# arca-2_0.net
KiCad netlist of a schematic drawn in EAGLE
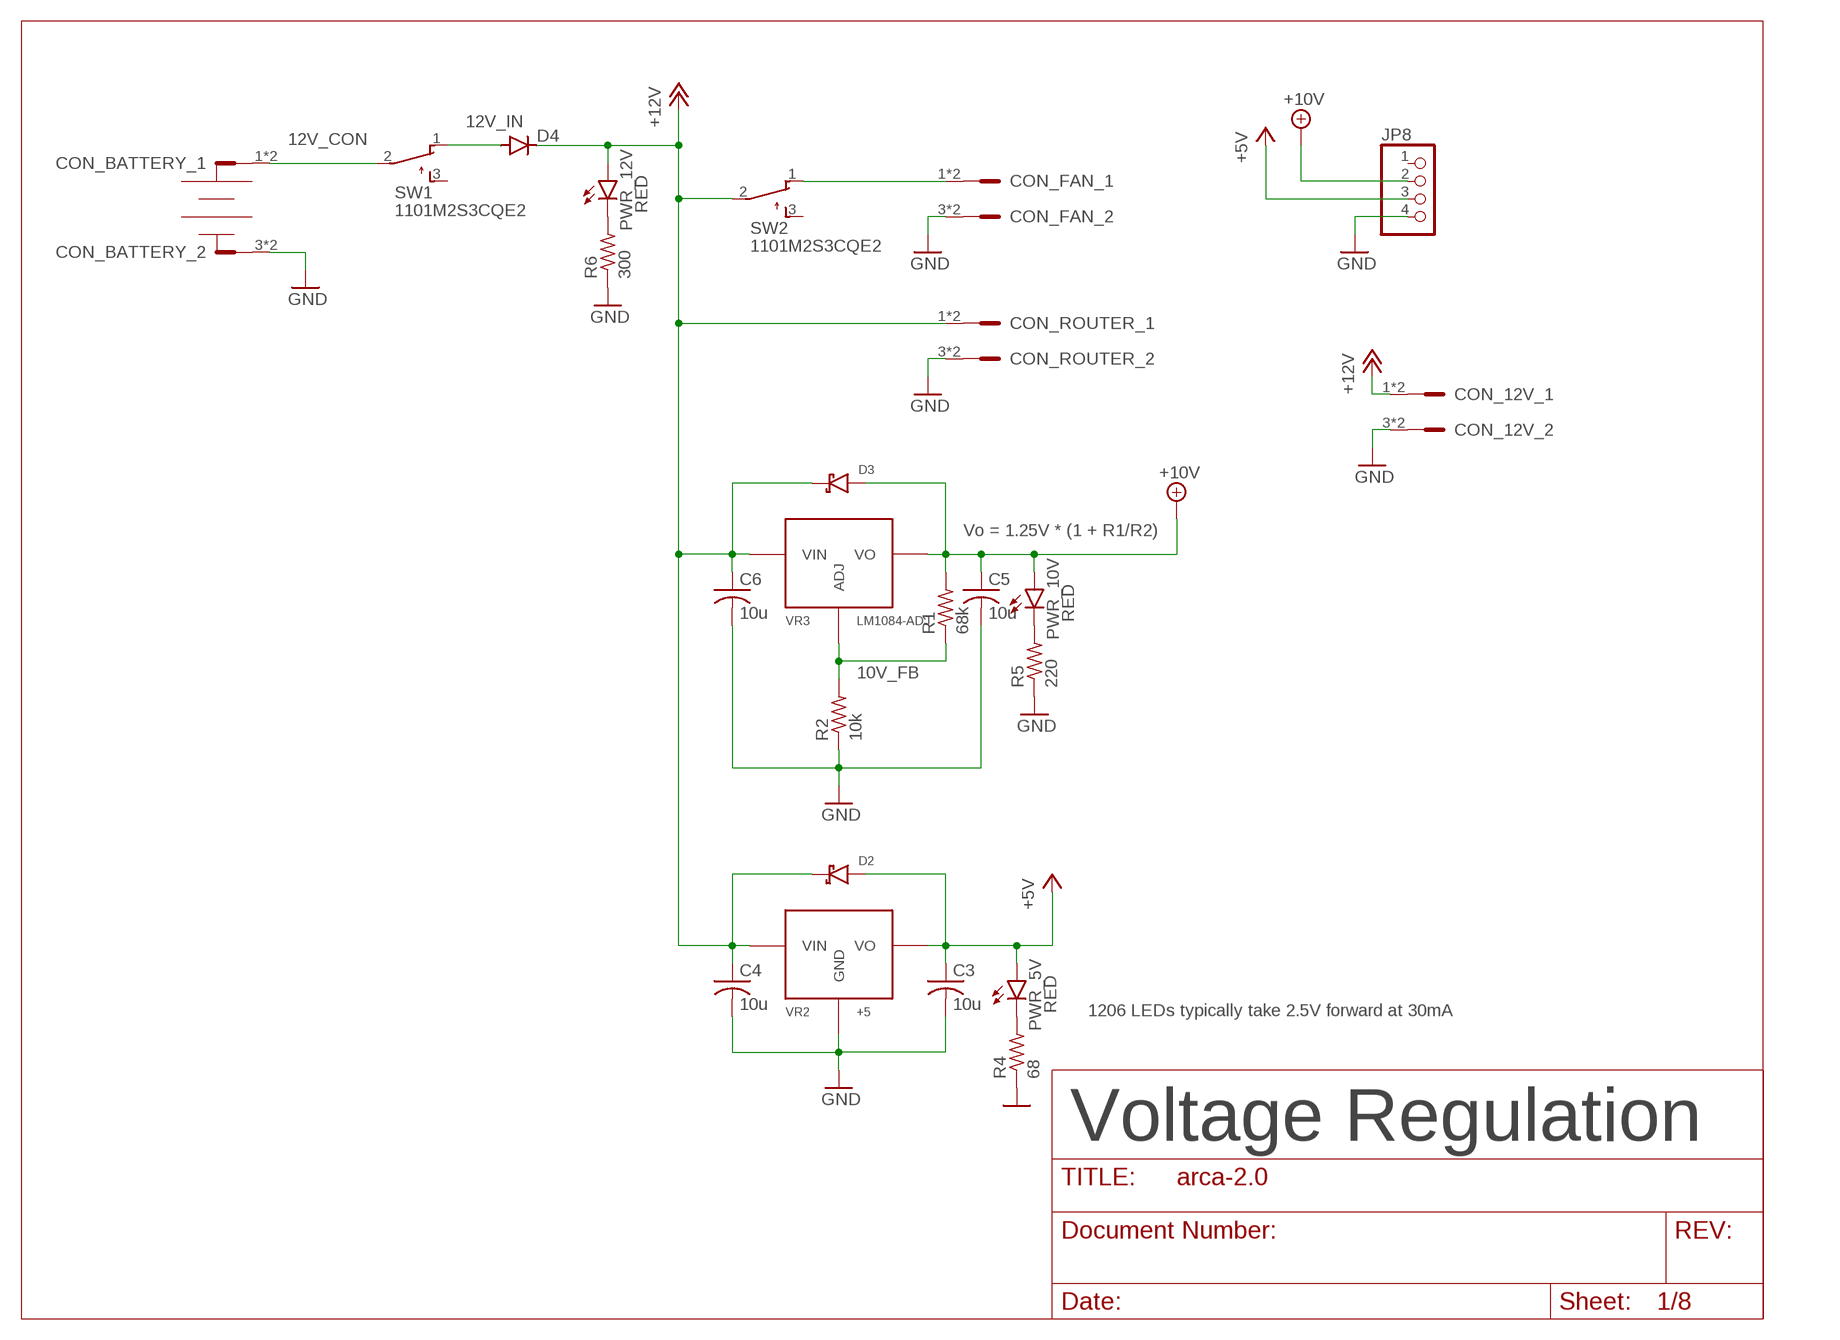
[diagram p0: schematic, sheet 1]
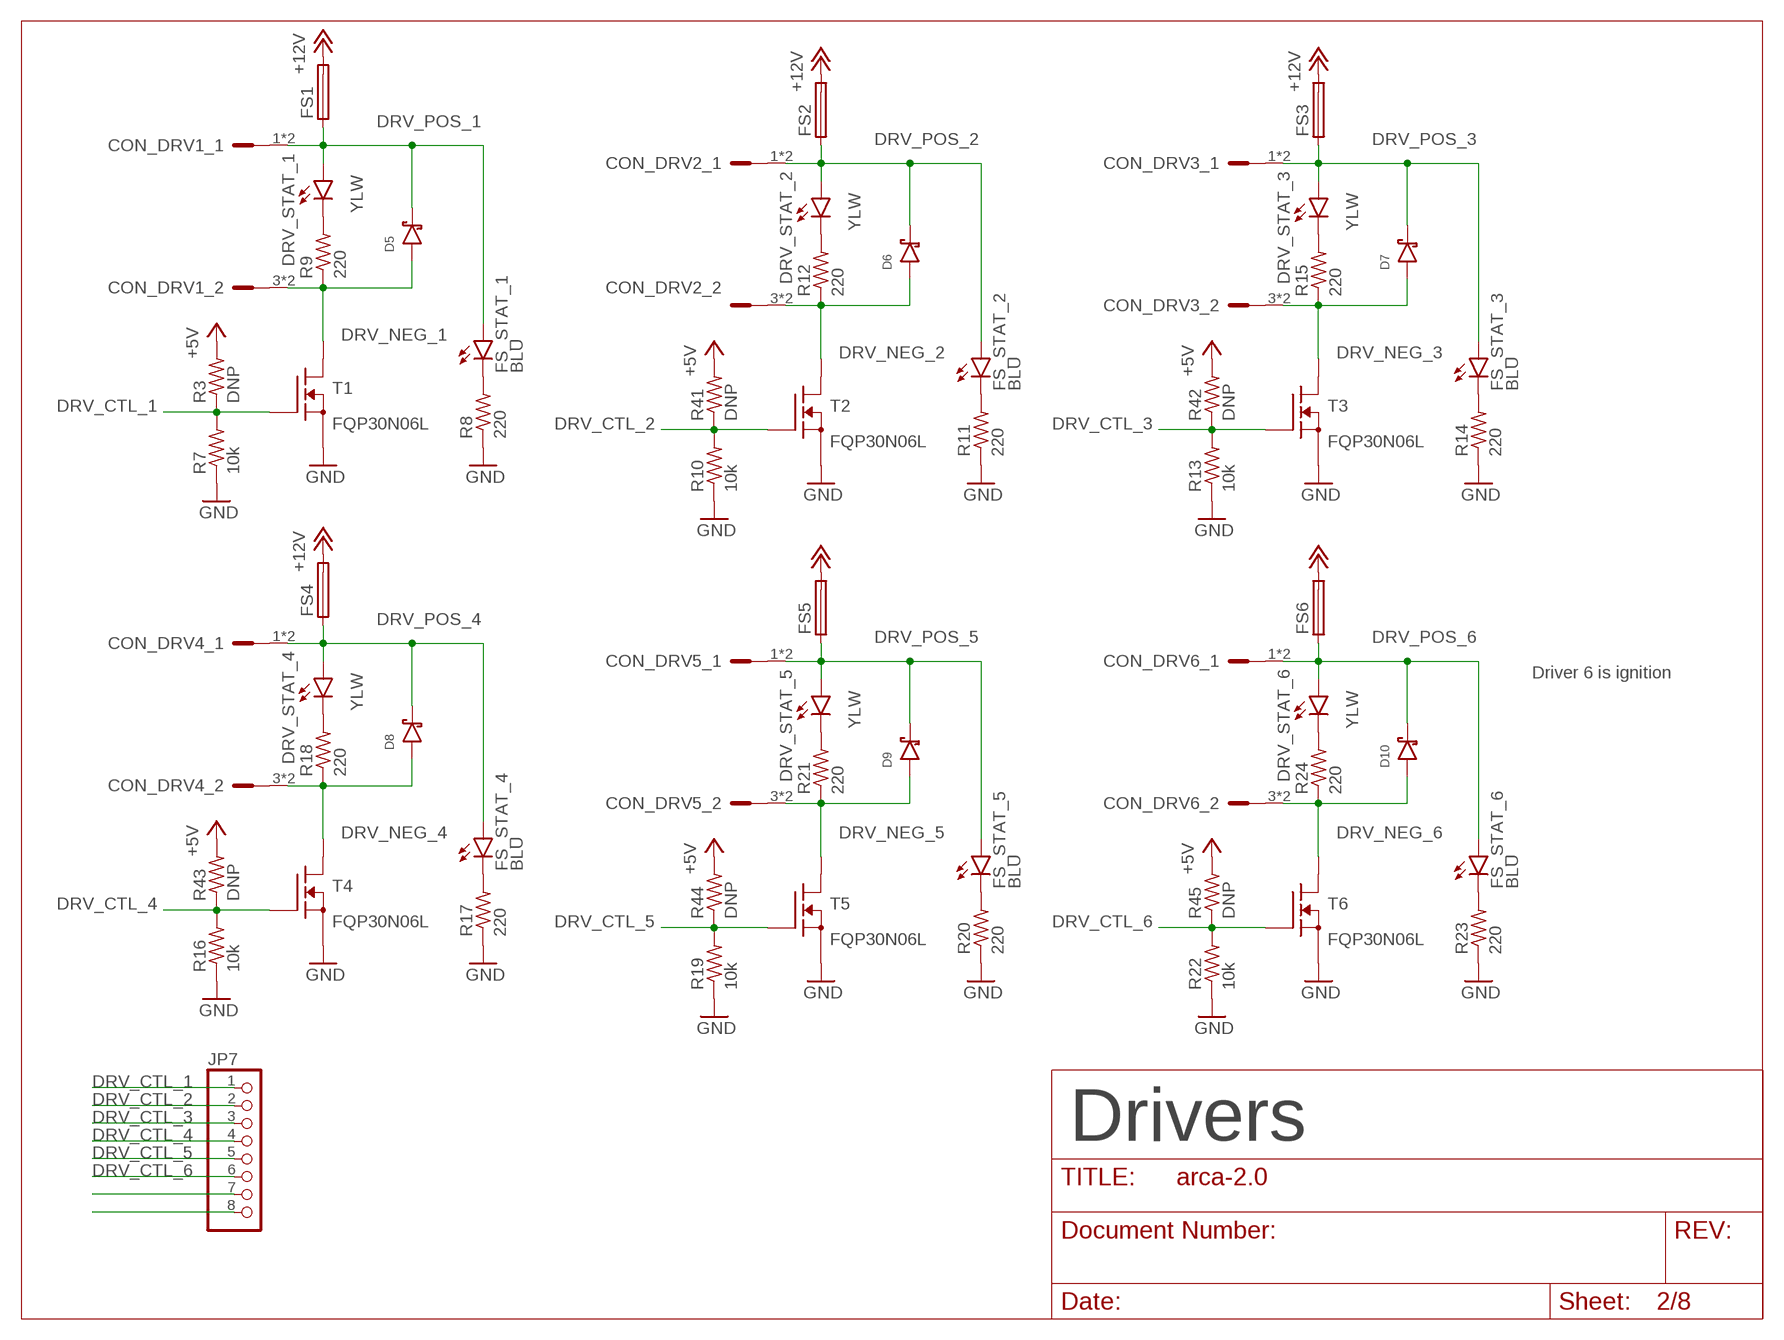
[diagram p1: schematic, sheet 2]
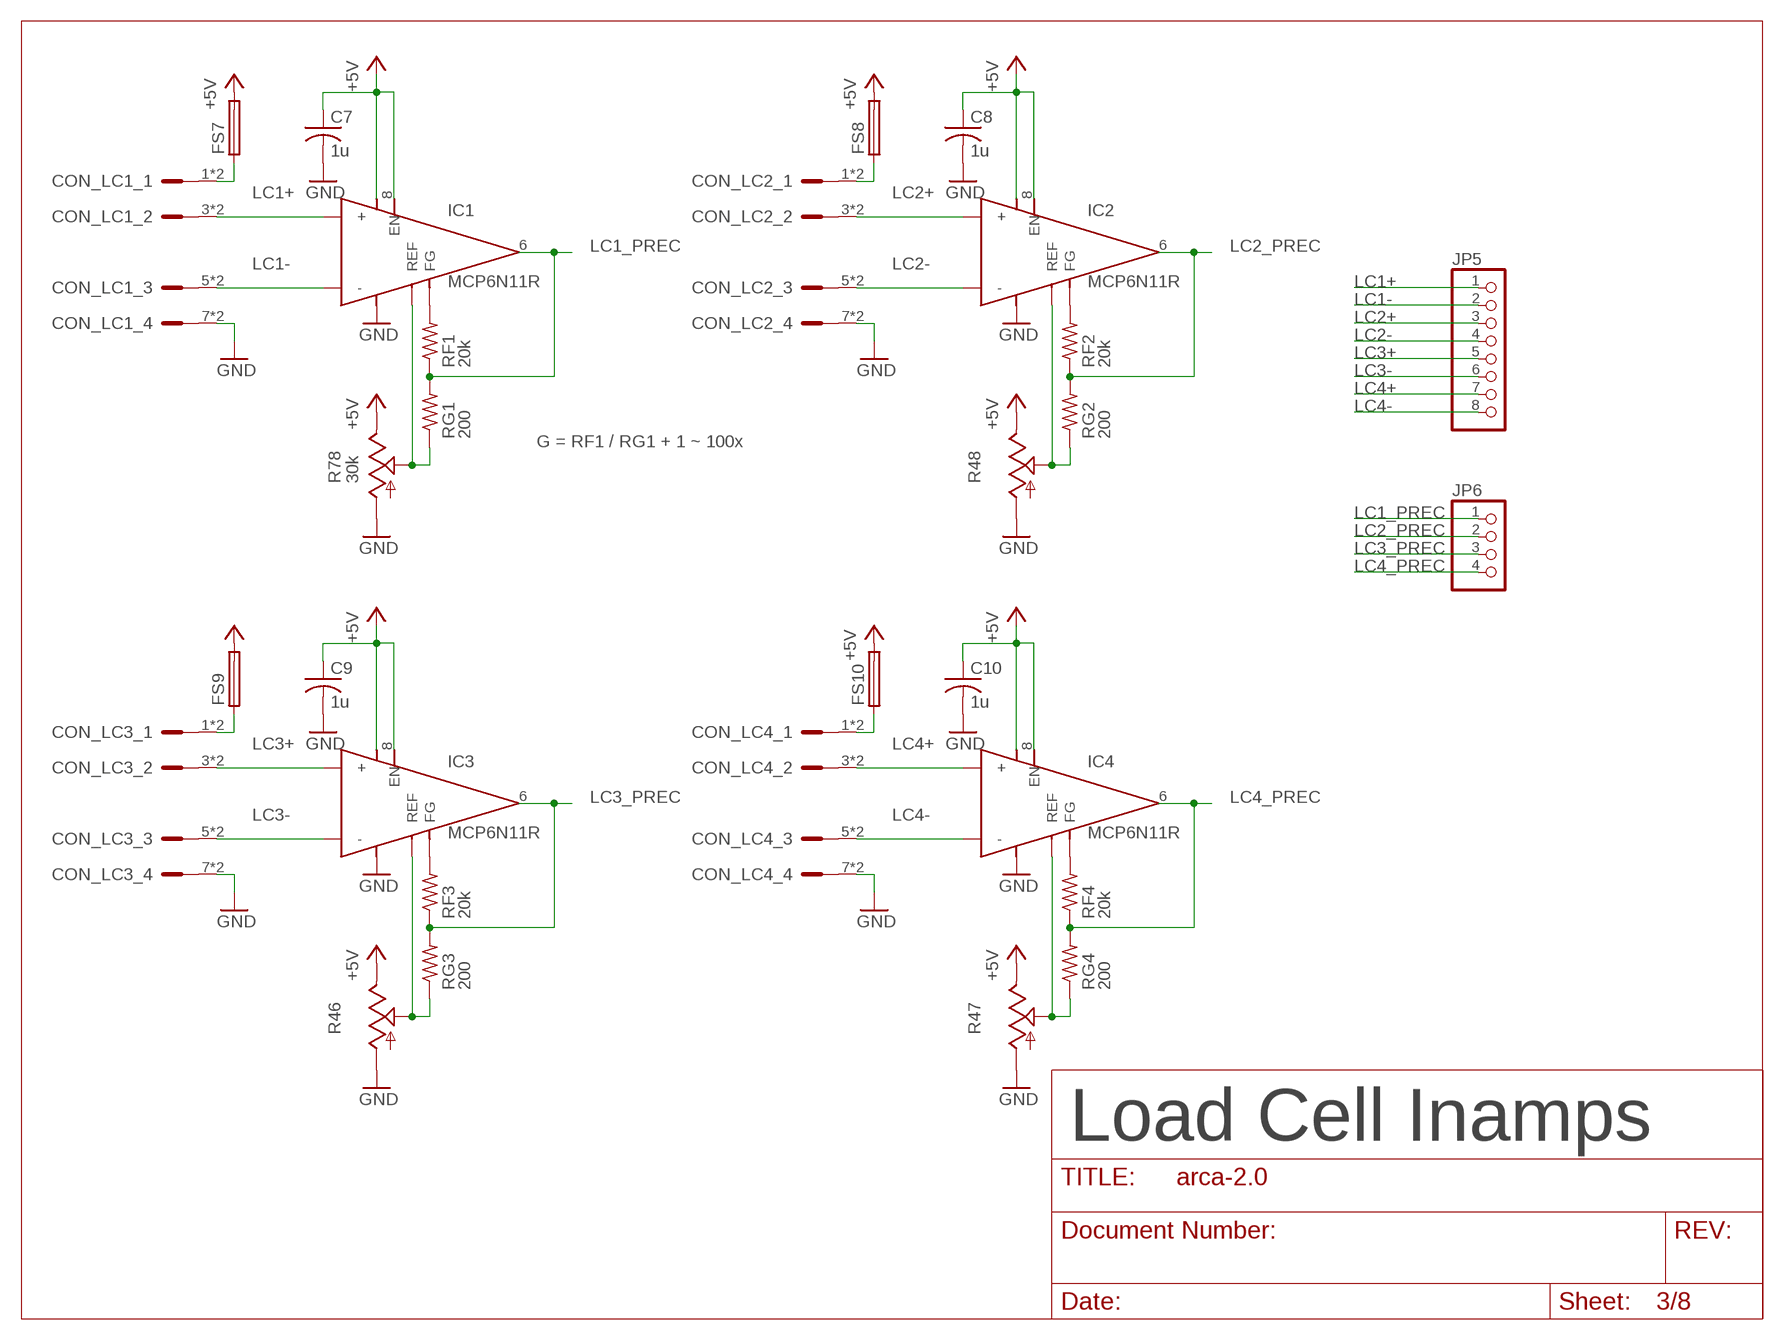
[diagram p2: schematic, sheet 3]
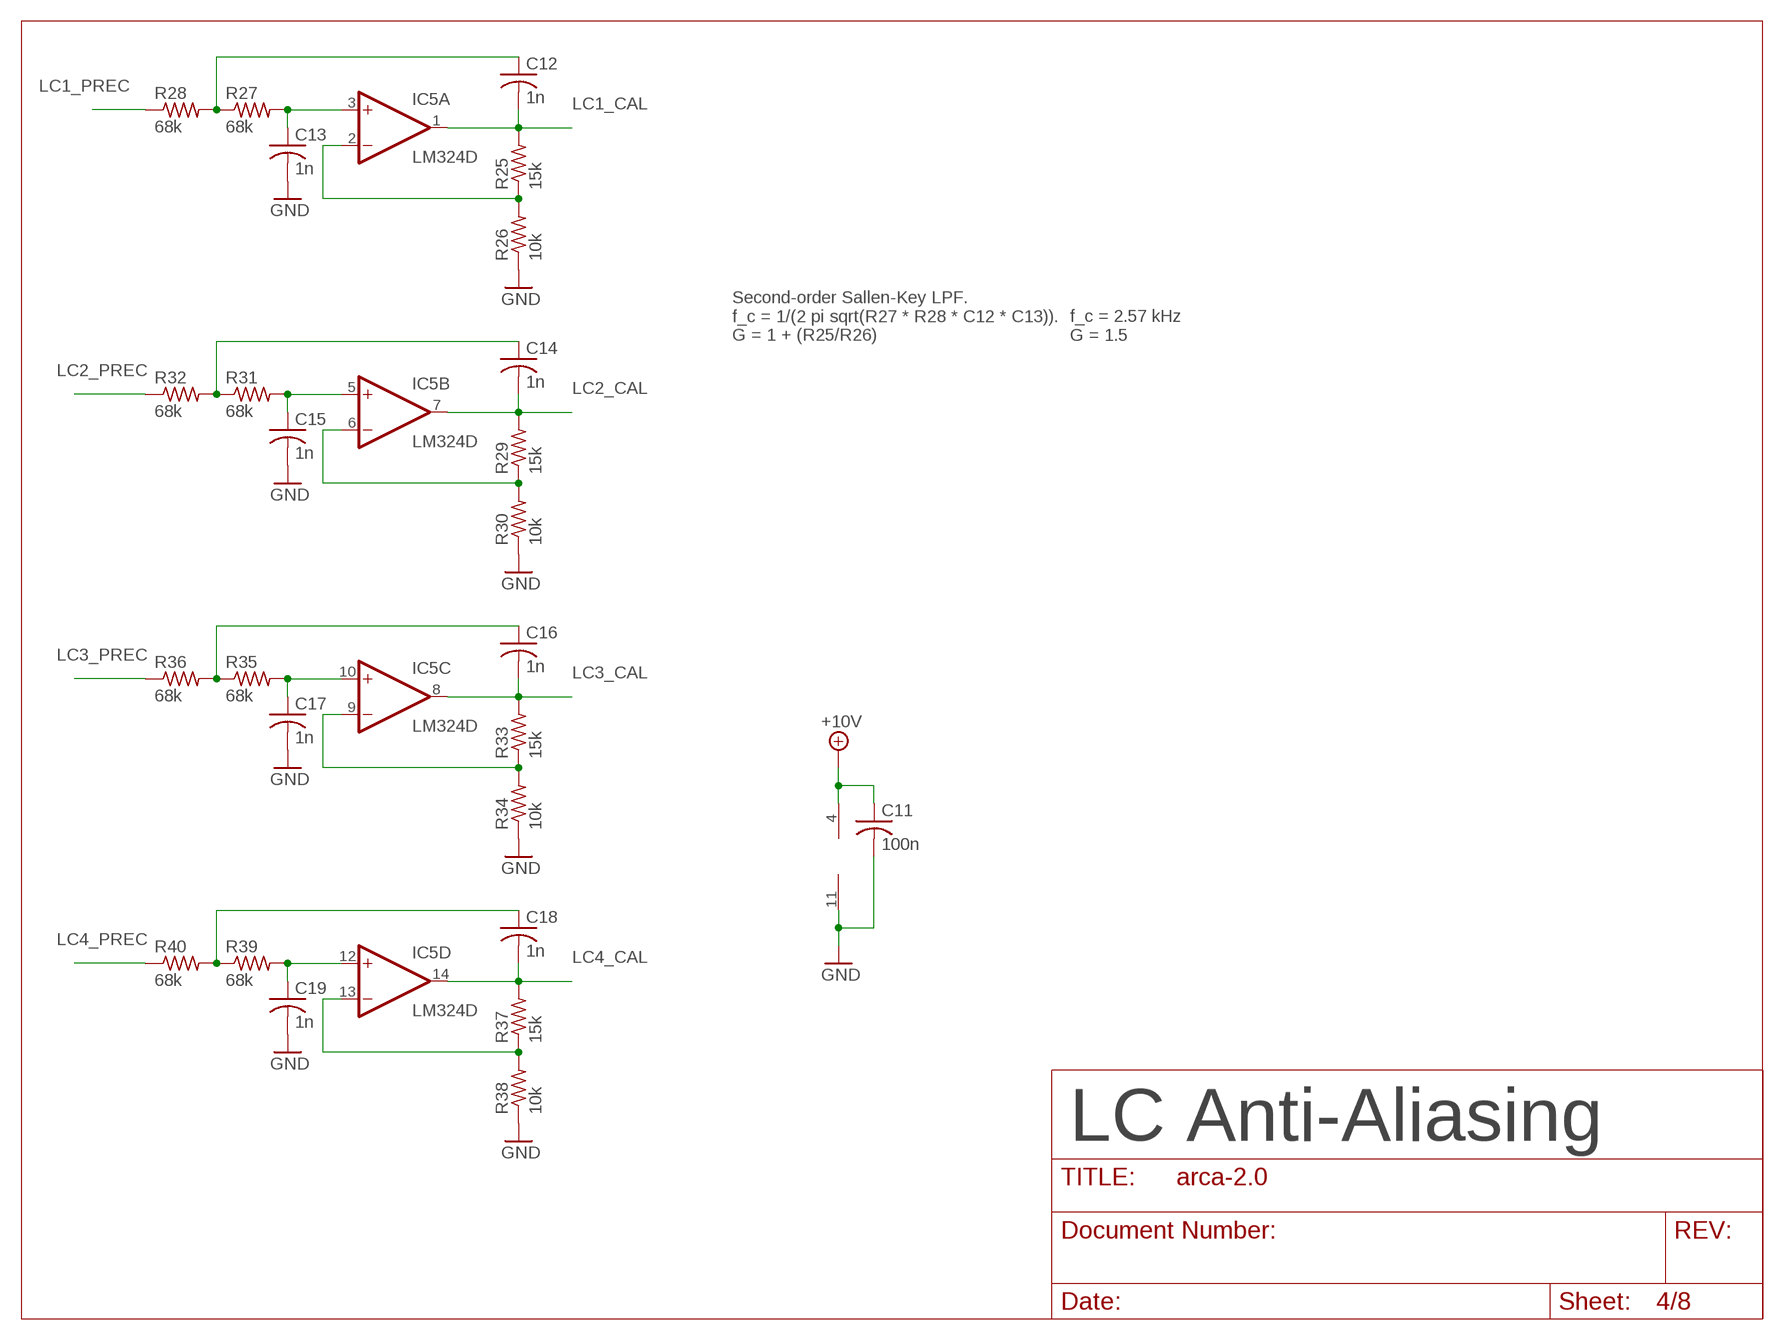
[diagram p3: schematic, sheet 4]
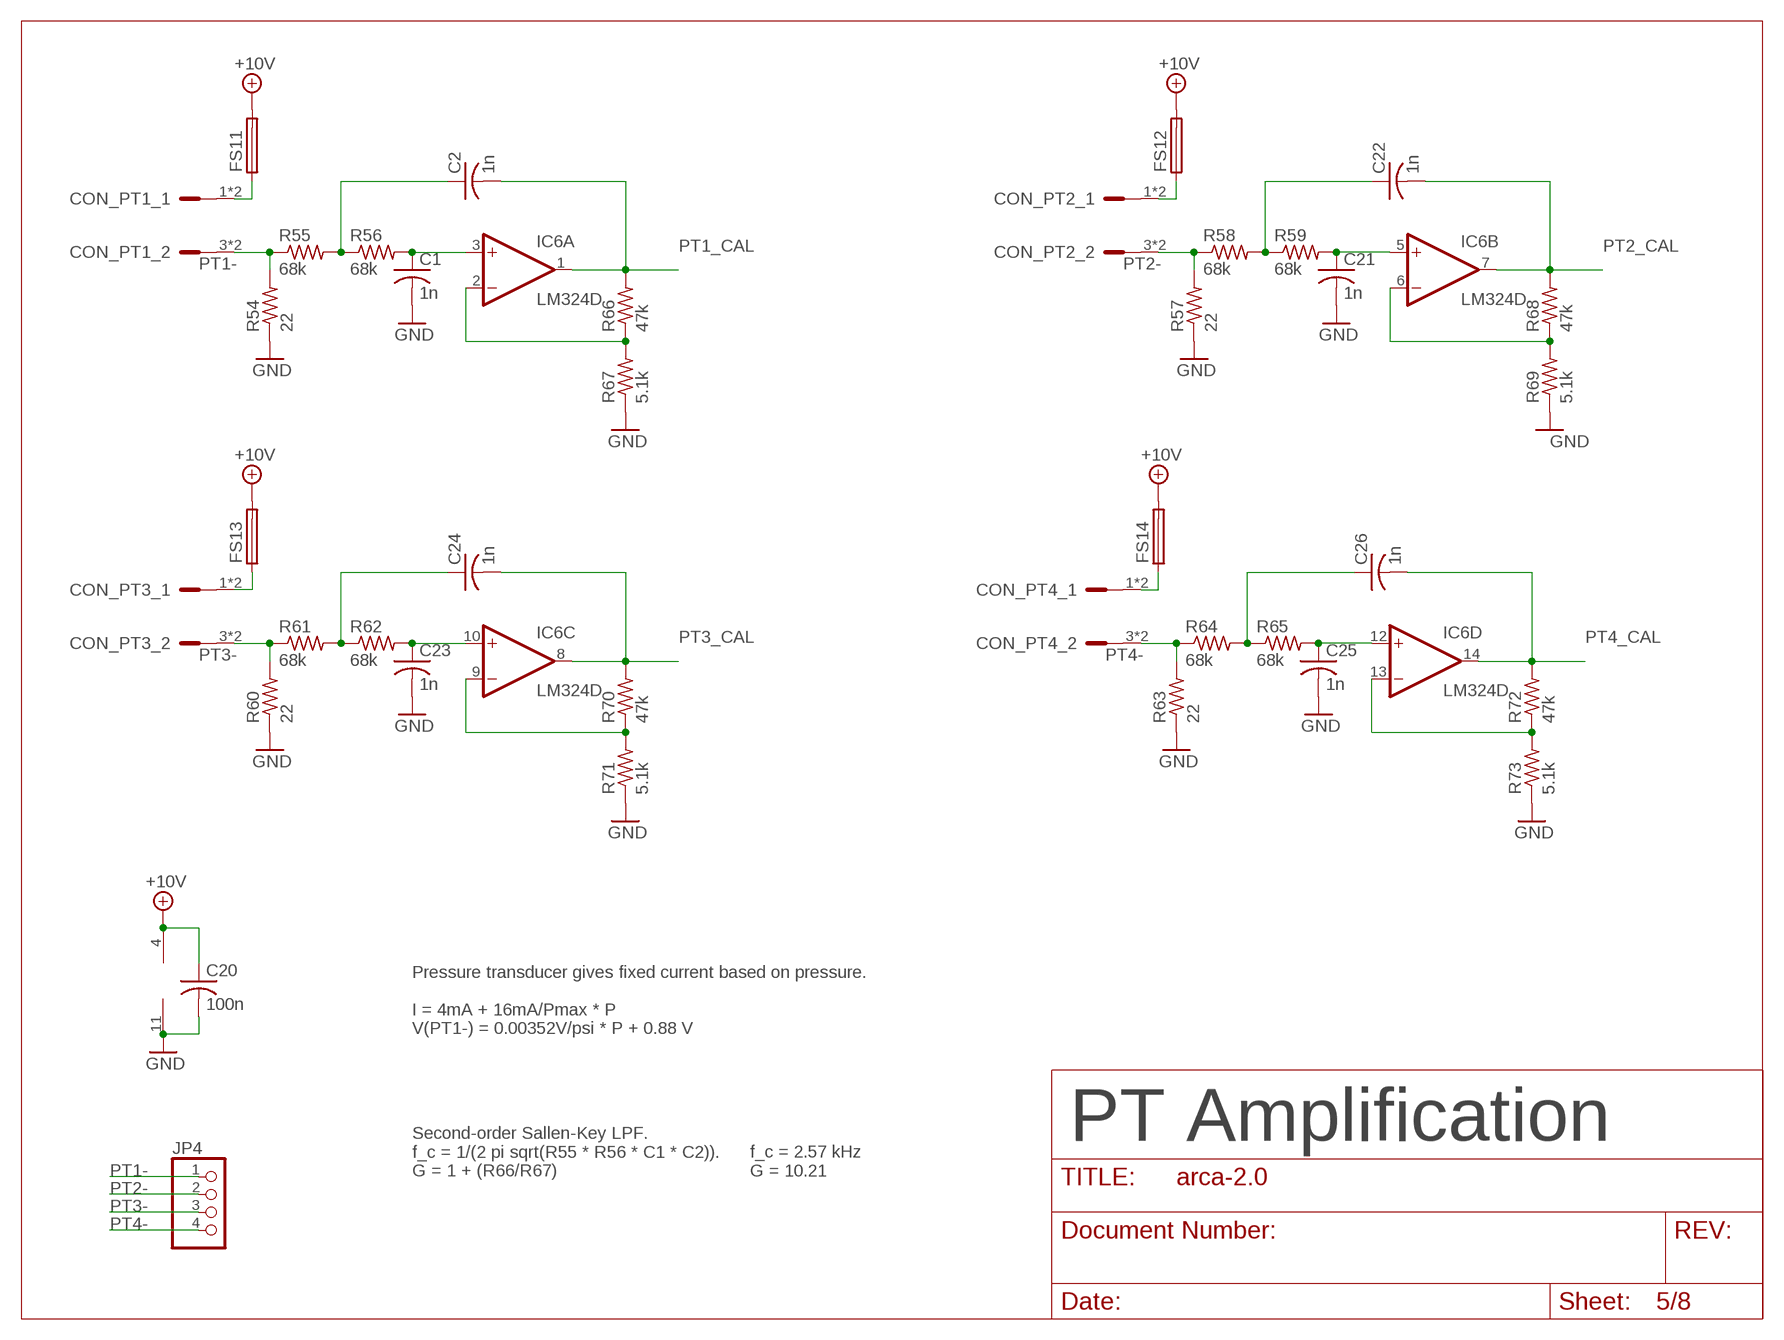
[diagram p4: schematic, sheet 5]
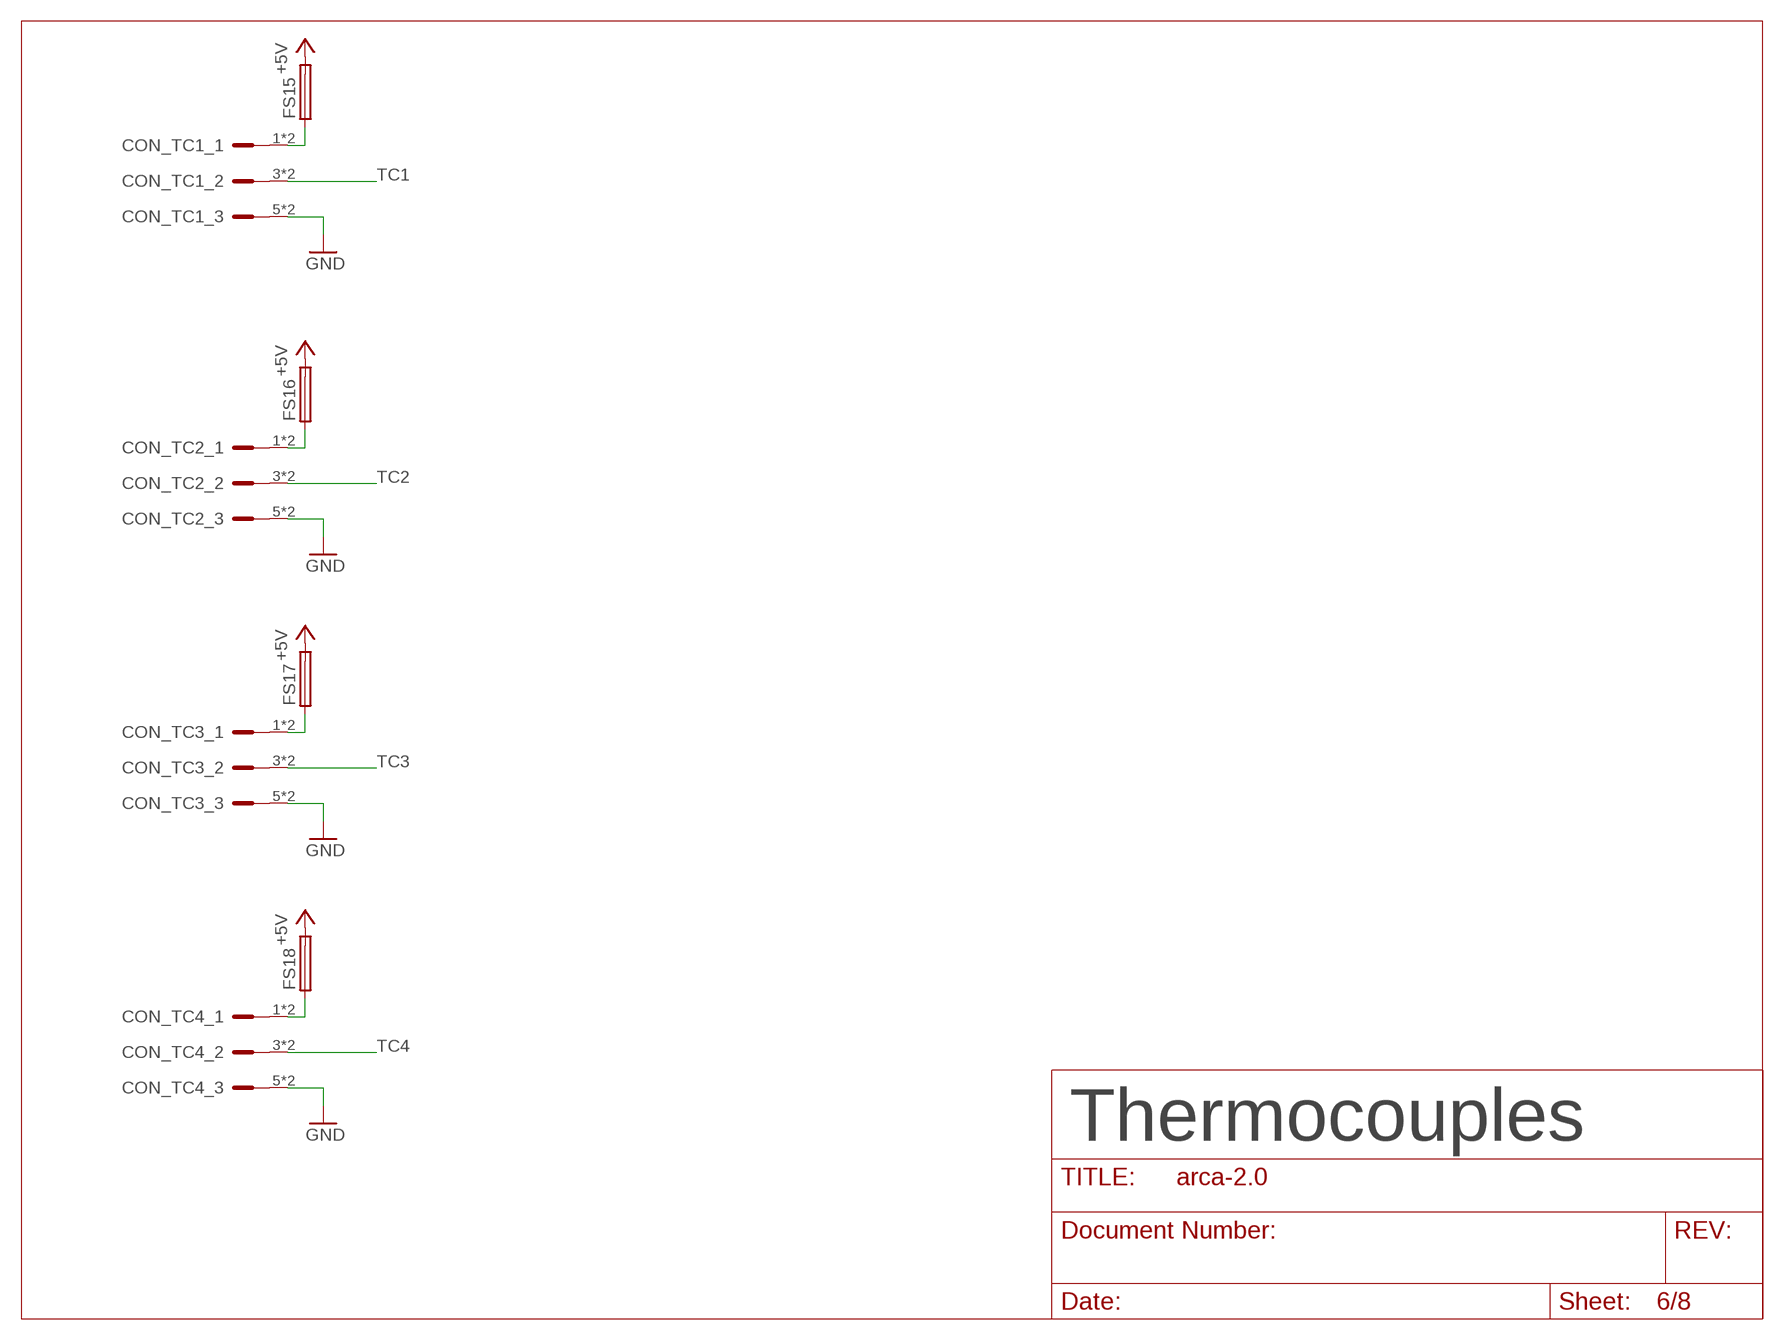
[diagram p5: schematic, sheet 6]
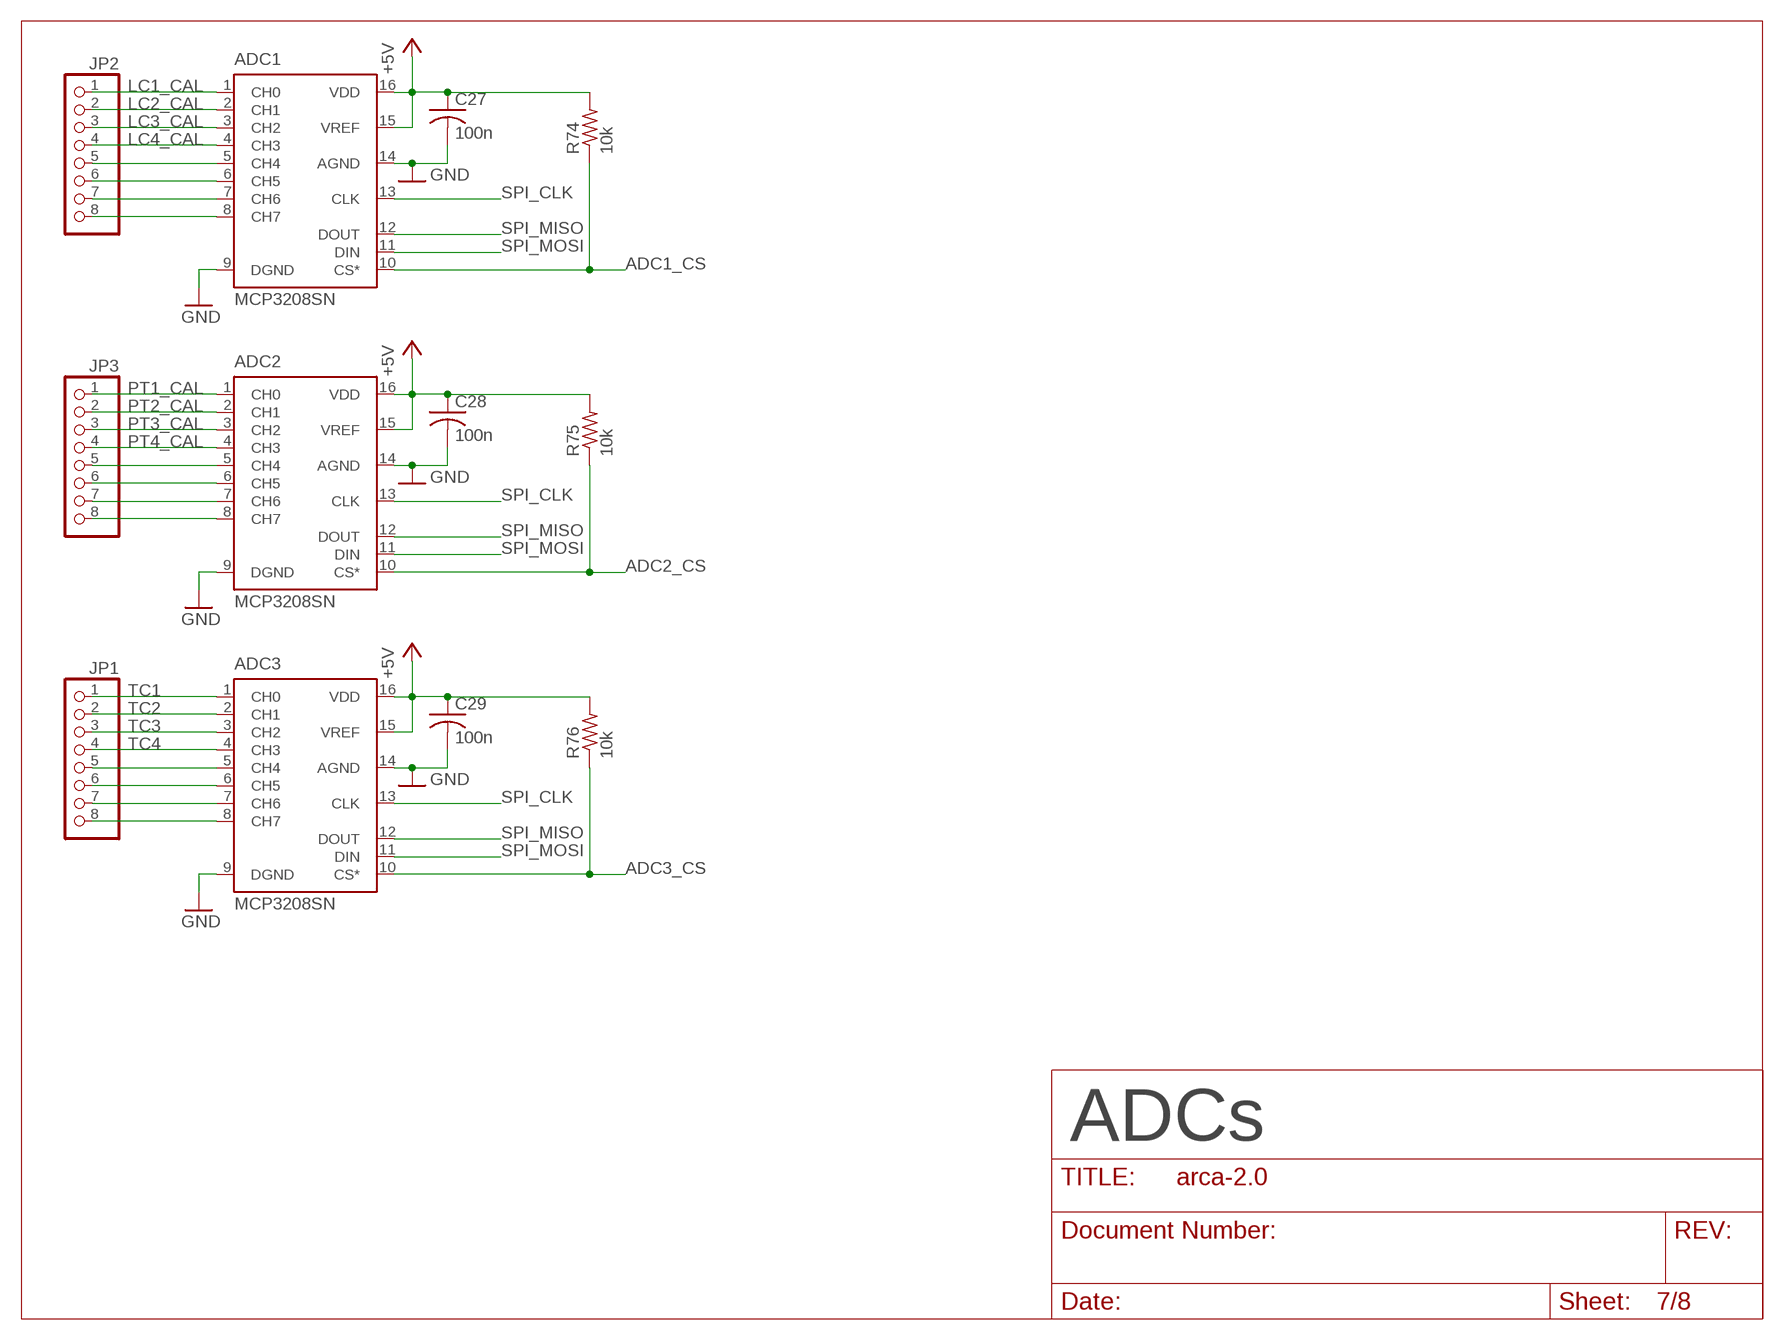
[diagram p6: schematic, sheet 7]
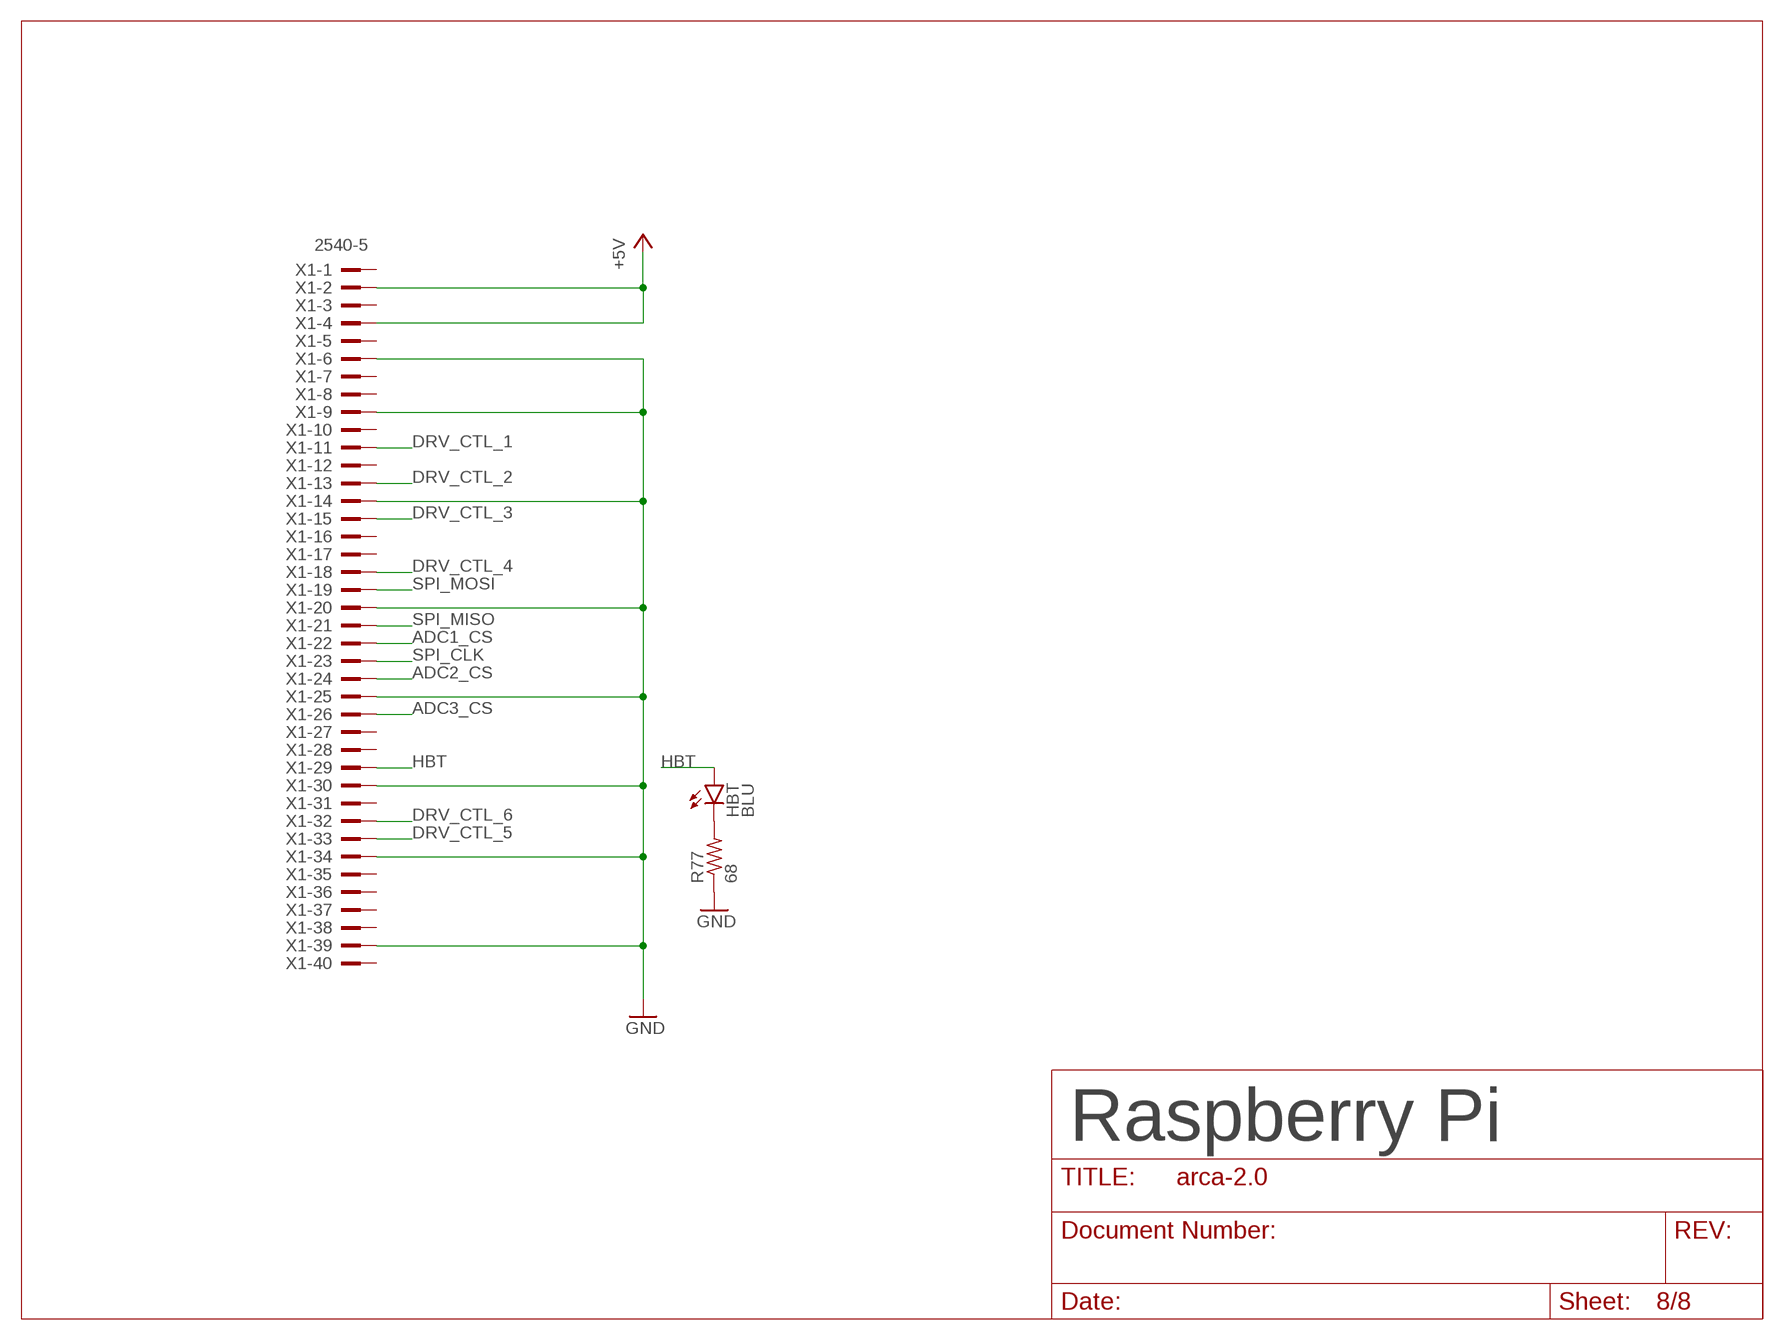
[diagram p7: schematic, sheet 8]

(export (version "E")
  (design (tool "Eeschema 10.0.6"))
  (components
    (comp (ref "HBT")
      (value "BLU")
      (footprint "eagle-import:CHIPLED_1206")
      (libsource (lib "eagle-import") (part "LEDCHIPLED_1206"))
    )
    (comp (ref "R77")
      (value "68")
      (footprint "eagle-import:R1206")
      (libsource (lib "eagle-import") (part "R-US_R1206"))
    )
    (comp (ref "X1")
      (value "2540-5")
      (footprint "eagle-import:PAK100_2500-5-40")
      (libsource (lib "eagle-import") (part "2540-5"))
    )
    (comp (ref "ADC1")
      (value "MCP3208SN")
      (footprint "eagle-import:SO-16")
      (fields (field (name "MF") "MICROCHIP") (field (name "MPN") "MCP3202-CI/SN"))
      (libsource (lib "eagle-import") (part "MCP3208SN"))
    )
    (comp (ref "ADC2")
      (value "MCP3208SN")
      (footprint "eagle-import:SO-16")
      (fields (field (name "MF") "MICROCHIP") (field (name "MPN") "MCP3202-CI/SN"))
      (libsource (lib "eagle-import") (part "MCP3208SN"))
    )
    (comp (ref "ADC3")
      (value "MCP3208SN")
      (footprint "eagle-import:SO-16")
      (fields (field (name "MF") "MICROCHIP") (field (name "MPN") "MCP3202-CI/SN"))
      (libsource (lib "eagle-import") (part "MCP3208SN"))
    )
    (comp (ref "C27")
      (value "100n")
      (footprint "eagle-import:C1206")
      (libsource (lib "eagle-import") (part "C-USC1206"))
    )
    (comp (ref "C28")
      (value "100n")
      (footprint "eagle-import:C1206")
      (libsource (lib "eagle-import") (part "C-USC1206"))
    )
    (comp (ref "C29")
      (value "100n")
      (footprint "eagle-import:C1206")
      (libsource (lib "eagle-import") (part "C-USC1206"))
    )
    (comp (ref "JP1")
      (value "PINHD-1X8")
      (footprint "eagle-import:1X08")
      (libsource (lib "eagle-import") (part "PINHD-1X8"))
    )
    (comp (ref "JP2")
      (value "PINHD-1X8")
      (footprint "eagle-import:1X08")
      (libsource (lib "eagle-import") (part "PINHD-1X8"))
    )
    (comp (ref "JP3")
      (value "PINHD-1X8")
      (footprint "eagle-import:1X08")
      (libsource (lib "eagle-import") (part "PINHD-1X8"))
    )
    (comp (ref "R74")
      (value "10k")
      (footprint "eagle-import:R1206")
      (libsource (lib "eagle-import") (part "R-US_R1206"))
    )
    (comp (ref "R75")
      (value "10k")
      (footprint "eagle-import:R1206")
      (libsource (lib "eagle-import") (part "R-US_R1206"))
    )
    (comp (ref "R76")
      (value "10k")
      (footprint "eagle-import:R1206")
      (libsource (lib "eagle-import") (part "R-US_R1206"))
    )
    (comp (ref "CON_TC1")
      (value "LPTA-3POS")
      (footprint "eagle-import:8.2X3")
      (libsource (lib "eagle-import") (part "LPTA-3POS"))
    )
    (comp (ref "CON_TC2")
      (value "LPTA-3POS")
      (footprint "eagle-import:8.2X3")
      (libsource (lib "eagle-import") (part "LPTA-3POS"))
    )
    (comp (ref "CON_TC3")
      (value "LPTA-3POS")
      (footprint "eagle-import:8.2X3")
      (libsource (lib "eagle-import") (part "LPTA-3POS"))
    )
    (comp (ref "CON_TC4")
      (value "LPTA-3POS")
      (footprint "eagle-import:8.2X3")
      (libsource (lib "eagle-import") (part "LPTA-3POS"))
    )
    (comp (ref "FS15")
      (value "HOLDER_3588-20")
      (footprint "eagle-import:3588-20")
      (libsource (lib "eagle-import") (part "HOLDER_3588-20"))
    )
    (comp (ref "FS16")
      (value "HOLDER_3588-20")
      (footprint "eagle-import:3588-20")
      (libsource (lib "eagle-import") (part "HOLDER_3588-20"))
    )
    (comp (ref "FS17")
      (value "HOLDER_3588-20")
      (footprint "eagle-import:3588-20")
      (libsource (lib "eagle-import") (part "HOLDER_3588-20"))
    )
    (comp (ref "FS18")
      (value "HOLDER_3588-20")
      (footprint "eagle-import:3588-20")
      (libsource (lib "eagle-import") (part "HOLDER_3588-20"))
    )
    (comp (ref "CON_DRV1")
      (value "LPTA-2POS")
      (footprint "eagle-import:8.2X2")
      (libsource (lib "eagle-import") (part "LPTA-2POS"))
    )
    (comp (ref "CON_DRV2")
      (value "LPTA-2POS")
      (footprint "eagle-import:8.2X2")
      (libsource (lib "eagle-import") (part "LPTA-2POS"))
    )
    (comp (ref "CON_DRV3")
      (value "LPTA-2POS")
      (footprint "eagle-import:8.2X2")
      (libsource (lib "eagle-import") (part "LPTA-2POS"))
    )
    (comp (ref "CON_DRV4")
      (value "LPTA-2POS")
      (footprint "eagle-import:8.2X2")
      (libsource (lib "eagle-import") (part "LPTA-2POS"))
    )
    (comp (ref "CON_DRV5")
      (value "LPTA-2POS")
      (footprint "eagle-import:8.2X2")
      (libsource (lib "eagle-import") (part "LPTA-2POS"))
    )
    (comp (ref "CON_DRV6")
      (value "LPTA-2POS")
      (footprint "eagle-import:8.2X2")
      (libsource (lib "eagle-import") (part "LPTA-2POS"))
    )
    (comp (ref "D5")
      (value "SS54")
      (footprint "eagle-import:SS_")
      (libsource (lib "eagle-import") (part "SS54"))
    )
    (comp (ref "D6")
      (value "SS54")
      (footprint "eagle-import:SS_")
      (libsource (lib "eagle-import") (part "SS54"))
    )
    (comp (ref "D7")
      (value "SS54")
      (footprint "eagle-import:SS_")
      (libsource (lib "eagle-import") (part "SS54"))
    )
    (comp (ref "D8")
      (value "SS54")
      (footprint "eagle-import:SS_")
      (libsource (lib "eagle-import") (part "SS54"))
    )
    (comp (ref "D9")
      (value "SS54")
      (footprint "eagle-import:SS_")
      (libsource (lib "eagle-import") (part "SS54"))
    )
    (comp (ref "D10")
      (value "SS54")
      (footprint "eagle-import:SS_")
      (libsource (lib "eagle-import") (part "SS54"))
    )
    (comp (ref "DRV_STAT_1")
      (value "YLW")
      (footprint "eagle-import:CHIPLED_1206")
      (libsource (lib "eagle-import") (part "LEDCHIPLED_1206"))
    )
    (comp (ref "DRV_STAT_2")
      (value "YLW")
      (footprint "eagle-import:CHIPLED_1206")
      (libsource (lib "eagle-import") (part "LEDCHIPLED_1206"))
    )
    (comp (ref "DRV_STAT_3")
      (value "YLW")
      (footprint "eagle-import:CHIPLED_1206")
      (libsource (lib "eagle-import") (part "LEDCHIPLED_1206"))
    )
    (comp (ref "DRV_STAT_4")
      (value "YLW")
      (footprint "eagle-import:CHIPLED_1206")
      (libsource (lib "eagle-import") (part "LEDCHIPLED_1206"))
    )
    (comp (ref "DRV_STAT_5")
      (value "YLW")
      (footprint "eagle-import:CHIPLED_1206")
      (libsource (lib "eagle-import") (part "LEDCHIPLED_1206"))
    )
    (comp (ref "DRV_STAT_6")
      (value "YLW")
      (footprint "eagle-import:CHIPLED_1206")
      (libsource (lib "eagle-import") (part "LEDCHIPLED_1206"))
    )
    (comp (ref "FS1")
      (value "HOLDER_3588-20")
      (footprint "eagle-import:3588-20")
      (libsource (lib "eagle-import") (part "HOLDER_3588-20"))
    )
    (comp (ref "FS2")
      (value "HOLDER_3588-20")
      (footprint "eagle-import:3588-20")
      (libsource (lib "eagle-import") (part "HOLDER_3588-20"))
    )
    (comp (ref "FS3")
      (value "HOLDER_3588-20")
      (footprint "eagle-import:3588-20")
      (libsource (lib "eagle-import") (part "HOLDER_3588-20"))
    )
    (comp (ref "FS4")
      (value "HOLDER_3588-20")
      (footprint "eagle-import:3588-20")
      (libsource (lib "eagle-import") (part "HOLDER_3588-20"))
    )
    (comp (ref "FS5")
      (value "HOLDER_3588-20")
      (footprint "eagle-import:3588-20")
      (libsource (lib "eagle-import") (part "HOLDER_3588-20"))
    )
    (comp (ref "FS6")
      (value "HOLDER_3588-20")
      (footprint "eagle-import:3588-20")
      (libsource (lib "eagle-import") (part "HOLDER_3588-20"))
    )
    (comp (ref "FS_STAT_1")
      (value "BLU")
      (footprint "eagle-import:CHIPLED_1206")
      (libsource (lib "eagle-import") (part "LEDCHIPLED_1206"))
    )
    (comp (ref "FS_STAT_2")
      (value "BLU")
      (footprint "eagle-import:CHIPLED_1206")
      (libsource (lib "eagle-import") (part "LEDCHIPLED_1206"))
    )
    (comp (ref "FS_STAT_3")
      (value "BLU")
      (footprint "eagle-import:CHIPLED_1206")
      (libsource (lib "eagle-import") (part "LEDCHIPLED_1206"))
    )
    (comp (ref "FS_STAT_4")
      (value "BLU")
      (footprint "eagle-import:CHIPLED_1206")
      (libsource (lib "eagle-import") (part "LEDCHIPLED_1206"))
    )
    (comp (ref "FS_STAT_5")
      (value "BLU")
      (footprint "eagle-import:CHIPLED_1206")
      (libsource (lib "eagle-import") (part "LEDCHIPLED_1206"))
    )
    (comp (ref "FS_STAT_6")
      (value "BLU")
      (footprint "eagle-import:CHIPLED_1206")
      (libsource (lib "eagle-import") (part "LEDCHIPLED_1206"))
    )
    (comp (ref "JP7")
      (value "PINHD-1X8")
      (footprint "eagle-import:1X08")
      (libsource (lib "eagle-import") (part "PINHD-1X8"))
    )
    (comp (ref "R3")
      (value "DNP")
      (footprint "eagle-import:R1206")
      (libsource (lib "eagle-import") (part "R-US_R1206"))
    )
    (comp (ref "R7")
      (value "10k")
      (footprint "eagle-import:R1206")
      (libsource (lib "eagle-import") (part "R-US_R1206"))
    )
    (comp (ref "R8")
      (value "220")
      (footprint "eagle-import:R1206")
      (libsource (lib "eagle-import") (part "R-US_R1206"))
    )
    (comp (ref "R9")
      (value "220")
      (footprint "eagle-import:R1206")
      (libsource (lib "eagle-import") (part "R-US_R1206"))
    )
    (comp (ref "R10")
      (value "10k")
      (footprint "eagle-import:R1206")
      (libsource (lib "eagle-import") (part "R-US_R1206"))
    )
    (comp (ref "R11")
      (value "220")
      (footprint "eagle-import:R1206")
      (libsource (lib "eagle-import") (part "R-US_R1206"))
    )
    (comp (ref "R12")
      (value "220")
      (footprint "eagle-import:R1206")
      (libsource (lib "eagle-import") (part "R-US_R1206"))
    )
    (comp (ref "R13")
      (value "10k")
      (footprint "eagle-import:R1206")
      (libsource (lib "eagle-import") (part "R-US_R1206"))
    )
    (comp (ref "R14")
      (value "220")
      (footprint "eagle-import:R1206")
      (libsource (lib "eagle-import") (part "R-US_R1206"))
    )
    (comp (ref "R15")
      (value "220")
      (footprint "eagle-import:R1206")
      (libsource (lib "eagle-import") (part "R-US_R1206"))
    )
    (comp (ref "R16")
      (value "10k")
      (footprint "eagle-import:R1206")
      (libsource (lib "eagle-import") (part "R-US_R1206"))
    )
    (comp (ref "R17")
      (value "220")
      (footprint "eagle-import:R1206")
      (libsource (lib "eagle-import") (part "R-US_R1206"))
    )
    (comp (ref "R18")
      (value "220")
      (footprint "eagle-import:R1206")
      (libsource (lib "eagle-import") (part "R-US_R1206"))
    )
    (comp (ref "R19")
      (value "10k")
      (footprint "eagle-import:R1206")
      (libsource (lib "eagle-import") (part "R-US_R1206"))
    )
    (comp (ref "R20")
      (value "220")
      (footprint "eagle-import:R1206")
      (libsource (lib "eagle-import") (part "R-US_R1206"))
    )
    (comp (ref "R21")
      (value "220")
      (footprint "eagle-import:R1206")
      (libsource (lib "eagle-import") (part "R-US_R1206"))
    )
    (comp (ref "R22")
      (value "10k")
      (footprint "eagle-import:R1206")
      (libsource (lib "eagle-import") (part "R-US_R1206"))
    )
    (comp (ref "R23")
      (value "220")
      (footprint "eagle-import:R1206")
      (libsource (lib "eagle-import") (part "R-US_R1206"))
    )
    (comp (ref "R24")
      (value "220")
      (footprint "eagle-import:R1206")
      (libsource (lib "eagle-import") (part "R-US_R1206"))
    )
    (comp (ref "R41")
      (value "DNP")
      (footprint "eagle-import:R1206")
      (libsource (lib "eagle-import") (part "R-US_R1206"))
    )
    (comp (ref "R42")
      (value "DNP")
      (footprint "eagle-import:R1206")
      (libsource (lib "eagle-import") (part "R-US_R1206"))
    )
    (comp (ref "R43")
      (value "DNP")
      (footprint "eagle-import:R1206")
      (libsource (lib "eagle-import") (part "R-US_R1206"))
    )
    (comp (ref "R44")
      (value "DNP")
      (footprint "eagle-import:R1206")
      (libsource (lib "eagle-import") (part "R-US_R1206"))
    )
    (comp (ref "R45")
      (value "DNP")
      (footprint "eagle-import:R1206")
      (libsource (lib "eagle-import") (part "R-US_R1206"))
    )
    (comp (ref "T1")
      (value "FQP30N06L")
      (footprint "eagle-import:TO220V")
      (libsource (lib "eagle-import") (part "FQP30N06L"))
    )
    (comp (ref "T2")
      (value "FQP30N06L")
      (footprint "eagle-import:TO220V")
      (libsource (lib "eagle-import") (part "FQP30N06L"))
    )
    (comp (ref "T3")
      (value "FQP30N06L")
      (footprint "eagle-import:TO220V")
      (libsource (lib "eagle-import") (part "FQP30N06L"))
    )
    (comp (ref "T4")
      (value "FQP30N06L")
      (footprint "eagle-import:TO220V")
      (libsource (lib "eagle-import") (part "FQP30N06L"))
    )
    (comp (ref "T5")
      (value "FQP30N06L")
      (footprint "eagle-import:TO220V")
      (libsource (lib "eagle-import") (part "FQP30N06L"))
    )
    (comp (ref "T6")
      (value "FQP30N06L")
      (footprint "eagle-import:TO220V")
      (libsource (lib "eagle-import") (part "FQP30N06L"))
    )
    (comp (ref "C1")
      (value "1n")
      (footprint "eagle-import:C1206")
      (libsource (lib "eagle-import") (part "C-USC1206"))
    )
    (comp (ref "C2")
      (value "1n")
      (footprint "eagle-import:C1206")
      (libsource (lib "eagle-import") (part "C-USC1206"))
    )
    (comp (ref "C20")
      (value "100n")
      (footprint "eagle-import:C1206")
      (libsource (lib "eagle-import") (part "C-USC1206"))
    )
    (comp (ref "C21")
      (value "1n")
      (footprint "eagle-import:C1206")
      (libsource (lib "eagle-import") (part "C-USC1206"))
    )
    (comp (ref "C22")
      (value "1n")
      (footprint "eagle-import:C1206")
      (libsource (lib "eagle-import") (part "C-USC1206"))
    )
    (comp (ref "C23")
      (value "1n")
      (footprint "eagle-import:C1206")
      (libsource (lib "eagle-import") (part "C-USC1206"))
    )
    (comp (ref "C24")
      (value "1n")
      (footprint "eagle-import:C1206")
      (libsource (lib "eagle-import") (part "C-USC1206"))
    )
    (comp (ref "C25")
      (value "1n")
      (footprint "eagle-import:C1206")
      (libsource (lib "eagle-import") (part "C-USC1206"))
    )
    (comp (ref "C26")
      (value "1n")
      (footprint "eagle-import:C1206")
      (libsource (lib "eagle-import") (part "C-USC1206"))
    )
    (comp (ref "CON_PT1")
      (value "LPTA-2POS")
      (footprint "eagle-import:8.2X2")
      (libsource (lib "eagle-import") (part "LPTA-2POS"))
    )
    (comp (ref "CON_PT2")
      (value "LPTA-2POS")
      (footprint "eagle-import:8.2X2")
      (libsource (lib "eagle-import") (part "LPTA-2POS"))
    )
    (comp (ref "CON_PT3")
      (value "LPTA-2POS")
      (footprint "eagle-import:8.2X2")
      (libsource (lib "eagle-import") (part "LPTA-2POS"))
    )
    (comp (ref "CON_PT4")
      (value "LPTA-2POS")
      (footprint "eagle-import:8.2X2")
      (libsource (lib "eagle-import") (part "LPTA-2POS"))
    )
    (comp (ref "FS11")
      (value "HOLDER_3588-20")
      (footprint "eagle-import:3588-20")
      (libsource (lib "eagle-import") (part "HOLDER_3588-20"))
    )
    (comp (ref "FS12")
      (value "HOLDER_3588-20")
      (footprint "eagle-import:3588-20")
      (libsource (lib "eagle-import") (part "HOLDER_3588-20"))
    )
    (comp (ref "FS13")
      (value "HOLDER_3588-20")
      (footprint "eagle-import:3588-20")
      (libsource (lib "eagle-import") (part "HOLDER_3588-20"))
    )
    (comp (ref "FS14")
      (value "HOLDER_3588-20")
      (footprint "eagle-import:3588-20")
      (libsource (lib "eagle-import") (part "HOLDER_3588-20"))
    )
    (comp (ref "IC6")
      (value "LM324D")
      (footprint "eagle-import:SO14")
      (libsource (lib "eagle-import") (part "LM324D"))
    )
    (comp (ref "JP4")
      (value "PINHD-1X4")
      (footprint "eagle-import:1X04")
      (libsource (lib "eagle-import") (part "PINHD-1X4"))
    )
    (comp (ref "R54")
      (value "22")
      (footprint "eagle-import:R1206")
      (libsource (lib "eagle-import") (part "R-US_R1206"))
    )
    (comp (ref "R55")
      (value "68k")
      (footprint "eagle-import:R1206")
      (libsource (lib "eagle-import") (part "R-US_R1206"))
    )
    (comp (ref "R56")
      (value "68k")
      (footprint "eagle-import:R1206")
      (libsource (lib "eagle-import") (part "R-US_R1206"))
    )
    (comp (ref "R57")
      (value "22")
      (footprint "eagle-import:R1206")
      (libsource (lib "eagle-import") (part "R-US_R1206"))
    )
    (comp (ref "R58")
      (value "68k")
      (footprint "eagle-import:R1206")
      (libsource (lib "eagle-import") (part "R-US_R1206"))
    )
    (comp (ref "R59")
      (value "68k")
      (footprint "eagle-import:R1206")
      (libsource (lib "eagle-import") (part "R-US_R1206"))
    )
    (comp (ref "R60")
      (value "22")
      (footprint "eagle-import:R1206")
      (libsource (lib "eagle-import") (part "R-US_R1206"))
    )
    (comp (ref "R61")
      (value "68k")
      (footprint "eagle-import:R1206")
      (libsource (lib "eagle-import") (part "R-US_R1206"))
    )
    (comp (ref "R62")
      (value "68k")
      (footprint "eagle-import:R1206")
      (libsource (lib "eagle-import") (part "R-US_R1206"))
    )
    (comp (ref "R63")
      (value "22")
      (footprint "eagle-import:R1206")
      (libsource (lib "eagle-import") (part "R-US_R1206"))
    )
    (comp (ref "R64")
      (value "68k")
      (footprint "eagle-import:R1206")
      (libsource (lib "eagle-import") (part "R-US_R1206"))
    )
    (comp (ref "R65")
      (value "68k")
      (footprint "eagle-import:R1206")
      (libsource (lib "eagle-import") (part "R-US_R1206"))
    )
    (comp (ref "R66")
      (value "47k")
      (footprint "eagle-import:R1206")
      (libsource (lib "eagle-import") (part "R-US_R1206"))
    )
    (comp (ref "R67")
      (value "5.1k")
      (footprint "eagle-import:R1206")
      (libsource (lib "eagle-import") (part "R-US_R1206"))
    )
    (comp (ref "R68")
      (value "47k")
      (footprint "eagle-import:R1206")
      (libsource (lib "eagle-import") (part "R-US_R1206"))
    )
    (comp (ref "R69")
      (value "5.1k")
      (footprint "eagle-import:R1206")
      (libsource (lib "eagle-import") (part "R-US_R1206"))
    )
    (comp (ref "R70")
      (value "47k")
      (footprint "eagle-import:R1206")
      (libsource (lib "eagle-import") (part "R-US_R1206"))
    )
    (comp (ref "R71")
      (value "5.1k")
      (footprint "eagle-import:R1206")
      (libsource (lib "eagle-import") (part "R-US_R1206"))
    )
    (comp (ref "R72")
      (value "47k")
      (footprint "eagle-import:R1206")
      (libsource (lib "eagle-import") (part "R-US_R1206"))
    )
    (comp (ref "R73")
      (value "5.1k")
      (footprint "eagle-import:R1206")
      (libsource (lib "eagle-import") (part "R-US_R1206"))
    )
    (comp (ref "C3")
      (value "10u")
      (footprint "eagle-import:C1206")
      (libsource (lib "eagle-import") (part "C-USC1206"))
    )
    (comp (ref "C4")
      (value "10u")
      (footprint "eagle-import:C1206")
      (libsource (lib "eagle-import") (part "C-USC1206"))
    )
    (comp (ref "C5")
      (value "10u")
      (footprint "eagle-import:C1206")
      (libsource (lib "eagle-import") (part "C-USC1206"))
    )
    (comp (ref "C6")
      (value "10u")
      (footprint "eagle-import:C1206")
      (libsource (lib "eagle-import") (part "C-USC1206"))
    )
    (comp (ref "CON_12V")
      (value "LPTA-2POS")
      (footprint "eagle-import:8.2X2")
      (libsource (lib "eagle-import") (part "LPTA-2POS"))
    )
    (comp (ref "CON_BATTERY")
      (value "LPTA-2POS")
      (footprint "eagle-import:8.2X2")
      (libsource (lib "eagle-import") (part "LPTA-2POS"))
    )
    (comp (ref "CON_FAN")
      (value "LPTA-2POS")
      (footprint "eagle-import:8.2X2")
      (libsource (lib "eagle-import") (part "LPTA-2POS"))
    )
    (comp (ref "CON_ROUTER")
      (value "LPTA-2POS")
      (footprint "eagle-import:8.2X2")
      (libsource (lib "eagle-import") (part "LPTA-2POS"))
    )
    (comp (ref "D2")
      (value "SS54")
      (footprint "eagle-import:SS_")
      (libsource (lib "eagle-import") (part "SS54"))
    )
    (comp (ref "D3")
      (value "SS54")
      (footprint "eagle-import:SS_")
      (libsource (lib "eagle-import") (part "SS54"))
    )
    (comp (ref "D4")
      (value "DIODE-DO201-15")
      (footprint "eagle-import:DO201-15")
      (libsource (lib "eagle-import") (part "DIODE-DO201-15"))
    )
    (comp (ref "JP8")
      (value "PINHD-1X4")
      (footprint "eagle-import:1X04")
      (libsource (lib "eagle-import") (part "PINHD-1X4"))
    )
    (comp (ref "PWR_5V")
      (value "RED")
      (footprint "eagle-import:CHIPLED_1206")
      (libsource (lib "eagle-import") (part "LEDCHIPLED_1206"))
    )
    (comp (ref "PWR_10V")
      (value "RED")
      (footprint "eagle-import:CHIPLED_1206")
      (libsource (lib "eagle-import") (part "LEDCHIPLED_1206"))
    )
    (comp (ref "PWR_12V")
      (value "RED")
      (footprint "eagle-import:CHIPLED_1206")
      (libsource (lib "eagle-import") (part "LEDCHIPLED_1206"))
    )
    (comp (ref "R1")
      (value "68k")
      (footprint "eagle-import:R1206")
      (libsource (lib "eagle-import") (part "R-US_R1206"))
    )
    (comp (ref "R2")
      (value "10k")
      (footprint "eagle-import:R1206")
      (libsource (lib "eagle-import") (part "R-US_R1206"))
    )
    (comp (ref "R4")
      (value "68")
      (footprint "eagle-import:R1206")
      (libsource (lib "eagle-import") (part "R-US_R1206"))
    )
    (comp (ref "R5")
      (value "220")
      (footprint "eagle-import:R1206")
      (libsource (lib "eagle-import") (part "R-US_R1206"))
    )
    (comp (ref "R6")
      (value "300")
      (footprint "eagle-import:R1206")
      (libsource (lib "eagle-import") (part "R-US_R1206"))
    )
    (comp (ref "SW1")
      (value "1101M2S3CQE2")
      (footprint "eagle-import:1101M2S3CQE2")
      (fields (field (name "COPYRIGHT") "Copyright (C) 2015 Accelerated Designs. All rights reserved"))
      (libsource (lib "eagle-import") (part "1101M2S3CQE2"))
    )
    (comp (ref "SW2")
      (value "1101M2S3CQE2")
      (footprint "eagle-import:1101M2S3CQE2")
      (fields (field (name "COPYRIGHT") "Copyright (C) 2015 Accelerated Designs. All rights reserved"))
      (libsource (lib "eagle-import") (part "1101M2S3CQE2"))
    )
    (comp (ref "VR2")
      (value "+5")
      (footprint "eagle-import:TO-263-3L")
      (libsource (lib "eagle-import") (part "LM1084"))
    )
    (comp (ref "VR3")
      (value "LM1084-ADJ")
      (footprint "eagle-import:TO-263-3L")
      (libsource (lib "eagle-import") (part "LM1084-ADJ"))
    )
    (comp (ref "C7")
      (value "1u")
      (footprint "eagle-import:C1206")
      (libsource (lib "eagle-import") (part "C-USC1206"))
    )
    (comp (ref "C8")
      (value "1u")
      (footprint "eagle-import:C1206")
      (libsource (lib "eagle-import") (part "C-USC1206"))
    )
    (comp (ref "C9")
      (value "1u")
      (footprint "eagle-import:C1206")
      (libsource (lib "eagle-import") (part "C-USC1206"))
    )
    (comp (ref "C10")
      (value "1u")
      (footprint "eagle-import:C1206")
      (libsource (lib "eagle-import") (part "C-USC1206"))
    )
    (comp (ref "CON_LC1")
      (value "LPTA-4POS")
      (footprint "eagle-import:8.2X4")
      (libsource (lib "eagle-import") (part "LPTA-4POS"))
    )
    (comp (ref "CON_LC2")
      (value "LPTA-4POS")
      (footprint "eagle-import:8.2X4")
      (libsource (lib "eagle-import") (part "LPTA-4POS"))
    )
    (comp (ref "CON_LC3")
      (value "LPTA-4POS")
      (footprint "eagle-import:8.2X4")
      (libsource (lib "eagle-import") (part "LPTA-4POS"))
    )
    (comp (ref "CON_LC4")
      (value "LPTA-4POS")
      (footprint "eagle-import:8.2X4")
      (libsource (lib "eagle-import") (part "LPTA-4POS"))
    )
    (comp (ref "FS7")
      (value "HOLDER_3588-20")
      (footprint "eagle-import:3588-20")
      (libsource (lib "eagle-import") (part "HOLDER_3588-20"))
    )
    (comp (ref "FS8")
      (value "HOLDER_3588-20")
      (footprint "eagle-import:3588-20")
      (libsource (lib "eagle-import") (part "HOLDER_3588-20"))
    )
    (comp (ref "FS9")
      (value "HOLDER_3588-20")
      (footprint "eagle-import:3588-20")
      (libsource (lib "eagle-import") (part "HOLDER_3588-20"))
    )
    (comp (ref "FS10")
      (value "HOLDER_3588-20")
      (footprint "eagle-import:3588-20")
      (libsource (lib "eagle-import") (part "HOLDER_3588-20"))
    )
    (comp (ref "IC1")
      (value "MCP6N11R")
      (footprint "eagle-import:SO-8")
      (fields (field (name "MPN") "AD620AR"))
      (libsource (lib "eagle-import") (part "MCP6N11R"))
    )
    (comp (ref "IC2")
      (value "MCP6N11R")
      (footprint "eagle-import:SO-8")
      (fields (field (name "MPN") "AD620AR"))
      (libsource (lib "eagle-import") (part "MCP6N11R"))
    )
    (comp (ref "IC3")
      (value "MCP6N11R")
      (footprint "eagle-import:SO-8")
      (fields (field (name "MPN") "AD620AR"))
      (libsource (lib "eagle-import") (part "MCP6N11R"))
    )
    (comp (ref "IC4")
      (value "MCP6N11R")
      (footprint "eagle-import:SO-8")
      (fields (field (name "MPN") "AD620AR"))
      (libsource (lib "eagle-import") (part "MCP6N11R"))
    )
    (comp (ref "JP5")
      (value "PINHD-1X8")
      (footprint "eagle-import:1X08")
      (libsource (lib "eagle-import") (part "PINHD-1X8"))
    )
    (comp (ref "JP6")
      (value "PINHD-1X4")
      (footprint "eagle-import:1X04")
      (libsource (lib "eagle-import") (part "PINHD-1X4"))
    )
    (comp (ref "R46")
      (value "TRIM_US-S64W")
      (footprint "eagle-import:S64W")
      (libsource (lib "eagle-import") (part "TRIM_US-S64W"))
    )
    (comp (ref "R47")
      (value "TRIM_US-S64W")
      (footprint "eagle-import:S64W")
      (libsource (lib "eagle-import") (part "TRIM_US-S64W"))
    )
    (comp (ref "R48")
      (value "TRIM_US-S64W")
      (footprint "eagle-import:S64W")
      (libsource (lib "eagle-import") (part "TRIM_US-S64W"))
    )
    (comp (ref "R78")
      (value "30k")
      (footprint "eagle-import:S64W")
      (libsource (lib "eagle-import") (part "TRIM_US-S64W"))
    )
    (comp (ref "RF1")
      (value "20k")
      (footprint "eagle-import:R1206")
      (libsource (lib "eagle-import") (part "R-US_R1206"))
    )
    (comp (ref "RF2")
      (value "20k")
      (footprint "eagle-import:R1206")
      (libsource (lib "eagle-import") (part "R-US_R1206"))
    )
    (comp (ref "RF3")
      (value "20k")
      (footprint "eagle-import:R1206")
      (libsource (lib "eagle-import") (part "R-US_R1206"))
    )
    (comp (ref "RF4")
      (value "20k")
      (footprint "eagle-import:R1206")
      (libsource (lib "eagle-import") (part "R-US_R1206"))
    )
    (comp (ref "RG1")
      (value "200")
      (footprint "eagle-import:R1206")
      (libsource (lib "eagle-import") (part "R-US_R1206"))
    )
    (comp (ref "RG2")
      (value "200")
      (footprint "eagle-import:R1206")
      (libsource (lib "eagle-import") (part "R-US_R1206"))
    )
    (comp (ref "RG3")
      (value "200")
      (footprint "eagle-import:R1206")
      (libsource (lib "eagle-import") (part "R-US_R1206"))
    )
    (comp (ref "RG4")
      (value "200")
      (footprint "eagle-import:R1206")
      (libsource (lib "eagle-import") (part "R-US_R1206"))
    )
    (comp (ref "C11")
      (value "100n")
      (footprint "eagle-import:C1206")
      (libsource (lib "eagle-import") (part "C-USC1206"))
    )
    (comp (ref "C12")
      (value "1n")
      (footprint "eagle-import:C1206")
      (libsource (lib "eagle-import") (part "C-USC1206"))
    )
    (comp (ref "C13")
      (value "1n")
      (footprint "eagle-import:C1206")
      (libsource (lib "eagle-import") (part "C-USC1206"))
    )
    (comp (ref "C14")
      (value "1n")
      (footprint "eagle-import:C1206")
      (libsource (lib "eagle-import") (part "C-USC1206"))
    )
    (comp (ref "C15")
      (value "1n")
      (footprint "eagle-import:C1206")
      (libsource (lib "eagle-import") (part "C-USC1206"))
    )
    (comp (ref "C16")
      (value "1n")
      (footprint "eagle-import:C1206")
      (libsource (lib "eagle-import") (part "C-USC1206"))
    )
    (comp (ref "C17")
      (value "1n")
      (footprint "eagle-import:C1206")
      (libsource (lib "eagle-import") (part "C-USC1206"))
    )
    (comp (ref "C18")
      (value "1n")
      (footprint "eagle-import:C1206")
      (libsource (lib "eagle-import") (part "C-USC1206"))
    )
    (comp (ref "C19")
      (value "1n")
      (footprint "eagle-import:C1206")
      (libsource (lib "eagle-import") (part "C-USC1206"))
    )
    (comp (ref "IC5")
      (value "LM324D")
      (footprint "eagle-import:SO14")
      (fields (field (name "SPICEPREFIX") "J"))
      (libsource (lib "eagle-import") (part "LM324D"))
    )
    (comp (ref "R25")
      (value "15k")
      (footprint "eagle-import:R1206")
      (libsource (lib "eagle-import") (part "R-US_R1206"))
    )
    (comp (ref "R26")
      (value "10k")
      (footprint "eagle-import:R1206")
      (libsource (lib "eagle-import") (part "R-US_R1206"))
    )
    (comp (ref "R27")
      (value "68k")
      (footprint "eagle-import:R1206")
      (libsource (lib "eagle-import") (part "R-US_R1206"))
    )
    (comp (ref "R28")
      (value "68k")
      (footprint "eagle-import:R1206")
      (libsource (lib "eagle-import") (part "R-US_R1206"))
    )
    (comp (ref "R29")
      (value "15k")
      (footprint "eagle-import:R1206")
      (libsource (lib "eagle-import") (part "R-US_R1206"))
    )
    (comp (ref "R30")
      (value "10k")
      (footprint "eagle-import:R1206")
      (libsource (lib "eagle-import") (part "R-US_R1206"))
    )
    (comp (ref "R31")
      (value "68k")
      (footprint "eagle-import:R1206")
      (libsource (lib "eagle-import") (part "R-US_R1206"))
    )
    (comp (ref "R32")
      (value "68k")
      (footprint "eagle-import:R1206")
      (libsource (lib "eagle-import") (part "R-US_R1206"))
    )
    (comp (ref "R33")
      (value "15k")
      (footprint "eagle-import:R1206")
      (libsource (lib "eagle-import") (part "R-US_R1206"))
    )
    (comp (ref "R34")
      (value "10k")
      (footprint "eagle-import:R1206")
      (libsource (lib "eagle-import") (part "R-US_R1206"))
    )
    (comp (ref "R35")
      (value "68k")
      (footprint "eagle-import:R1206")
      (libsource (lib "eagle-import") (part "R-US_R1206"))
    )
    (comp (ref "R36")
      (value "68k")
      (footprint "eagle-import:R1206")
      (libsource (lib "eagle-import") (part "R-US_R1206"))
    )
    (comp (ref "R37")
      (value "15k")
      (footprint "eagle-import:R1206")
      (libsource (lib "eagle-import") (part "R-US_R1206"))
    )
    (comp (ref "R38")
      (value "10k")
      (footprint "eagle-import:R1206")
      (libsource (lib "eagle-import") (part "R-US_R1206"))
    )
    (comp (ref "R39")
      (value "68k")
      (footprint "eagle-import:R1206")
      (libsource (lib "eagle-import") (part "R-US_R1206"))
    )
    (comp (ref "R40")
      (value "68k")
      (footprint "eagle-import:R1206")
      (libsource (lib "eagle-import") (part "R-US_R1206"))
    )
  )
  (nets
    (net (code "1") (name "+5V") (class "Default")
      (node (ref "ADC1") (pin "15") (pinfunction "VREF_15") (pintype "bidirectional"))
      (node (ref "ADC1") (pin "16") (pinfunction "VDD_16") (pintype "bidirectional"))
      (node (ref "ADC2") (pin "15") (pinfunction "VREF_15") (pintype "bidirectional"))
      (node (ref "ADC2") (pin "16") (pinfunction "VDD_16") (pintype "bidirectional"))
      (node (ref "ADC3") (pin "15") (pinfunction "VREF_15") (pintype "bidirectional"))
      (node (ref "ADC3") (pin "16") (pinfunction "VDD_16") (pintype "bidirectional"))
      (node (ref "C10") (pin "1") (pinfunction "1_1") (pintype "passive"))
      (node (ref "C27") (pin "1") (pinfunction "1_1") (pintype "passive"))
      (node (ref "C28") (pin "1") (pinfunction "1_1") (pintype "passive"))
      (node (ref "C29") (pin "1") (pinfunction "1_1") (pintype "passive"))
      (node (ref "C3") (pin "1") (pinfunction "1_1") (pintype "passive"))
      (node (ref "C7") (pin "1") (pinfunction "1_1") (pintype "passive"))
      (node (ref "C8") (pin "1") (pinfunction "1_1") (pintype "passive"))
      (node (ref "C9") (pin "1") (pinfunction "1_1") (pintype "passive"))
      (node (ref "D2") (pin "P$2") (pinfunction "P$2_P$2") (pintype "bidirectional"))
      (node (ref "FS10") (pin "P$3") (pinfunction "2_P$3") (pintype "passive"))
      (node (ref "FS10") (pin "P$4") (pinfunction "2_P$4") (pintype "passive"))
      (node (ref "FS15") (pin "P$3") (pinfunction "2_P$3") (pintype "passive"))
      (node (ref "FS15") (pin "P$4") (pinfunction "2_P$4") (pintype "passive"))
      (node (ref "FS16") (pin "P$3") (pinfunction "2_P$3") (pintype "passive"))
      (node (ref "FS16") (pin "P$4") (pinfunction "2_P$4") (pintype "passive"))
      (node (ref "FS17") (pin "P$3") (pinfunction "2_P$3") (pintype "passive"))
      (node (ref "FS17") (pin "P$4") (pinfunction "2_P$4") (pintype "passive"))
      (node (ref "FS18") (pin "P$3") (pinfunction "2_P$3") (pintype "passive"))
      (node (ref "FS18") (pin "P$4") (pinfunction "2_P$4") (pintype "passive"))
      (node (ref "FS7") (pin "P$3") (pinfunction "2_P$3") (pintype "passive"))
      (node (ref "FS7") (pin "P$4") (pinfunction "2_P$4") (pintype "passive"))
      (node (ref "FS8") (pin "P$3") (pinfunction "2_P$3") (pintype "passive"))
      (node (ref "FS8") (pin "P$4") (pinfunction "2_P$4") (pintype "passive"))
      (node (ref "FS9") (pin "P$3") (pinfunction "2_P$3") (pintype "passive"))
      (node (ref "FS9") (pin "P$4") (pinfunction "2_P$4") (pintype "passive"))
      (node (ref "IC1") (pin "7") (pinfunction "+V_7") (pintype "power_in"))
      (node (ref "IC1") (pin "8") (pinfunction "EN_8") (pintype "input"))
      (node (ref "IC2") (pin "7") (pinfunction "+V_7") (pintype "power_in"))
      (node (ref "IC2") (pin "8") (pinfunction "EN_8") (pintype "input"))
      (node (ref "IC3") (pin "7") (pinfunction "+V_7") (pintype "power_in"))
      (node (ref "IC3") (pin "8") (pinfunction "EN_8") (pintype "input"))
      (node (ref "IC4") (pin "7") (pinfunction "+V_7") (pintype "power_in"))
      (node (ref "IC4") (pin "8") (pinfunction "EN_8") (pintype "input"))
      (node (ref "JP8") (pin "3") (pinfunction "3_3") (pintype "passive"))
      (node (ref "PWR_5V") (pin "A") (pinfunction "A_A") (pintype "passive"))
      (node (ref "R3") (pin "2") (pinfunction "2_2") (pintype "passive"))
      (node (ref "R41") (pin "2") (pinfunction "2_2") (pintype "passive"))
      (node (ref "R42") (pin "2") (pinfunction "2_2") (pintype "passive"))
      (node (ref "R43") (pin "2") (pinfunction "2_2") (pintype "passive"))
      (node (ref "R44") (pin "2") (pinfunction "2_2") (pintype "passive"))
      (node (ref "R45") (pin "2") (pinfunction "2_2") (pintype "passive"))
      (node (ref "R46") (pin "E") (pinfunction "E_E") (pintype "passive"))
      (node (ref "R47") (pin "E") (pinfunction "E_E") (pintype "passive"))
      (node (ref "R48") (pin "E") (pinfunction "E_E") (pintype "passive"))
      (node (ref "R74") (pin "2") (pinfunction "2_2") (pintype "passive"))
      (node (ref "R75") (pin "2") (pinfunction "2_2") (pintype "passive"))
      (node (ref "R76") (pin "2") (pinfunction "2_2") (pintype "passive"))
      (node (ref "R78") (pin "E") (pinfunction "E_E") (pintype "passive"))
      (node (ref "VR2") (pin "P$2") (pinfunction "VO_P$2") (pintype "bidirectional"))
      (node (ref "VR2") (pin "P$4") (pinfunction "VO_P$4") (pintype "bidirectional"))
      (node (ref "VR2") (pin "P$5") (pinfunction "VO_P$5") (pintype "bidirectional"))
      (node (ref "X1") (pin "2") (pinfunction "KL_2") (pintype "passive"))
      (node (ref "X1") (pin "4") (pinfunction "KL_4") (pintype "passive"))
    )
    (net (code "2") (name "+10V") (class "Default")
      (node (ref "C11") (pin "1") (pinfunction "1_1") (pintype "passive"))
      (node (ref "C20") (pin "1") (pinfunction "1_1") (pintype "passive"))
      (node (ref "C5") (pin "1") (pinfunction "1_1") (pintype "passive"))
      (node (ref "D3") (pin "P$2") (pinfunction "P$2_P$2") (pintype "bidirectional"))
      (node (ref "FS11") (pin "P$3") (pinfunction "2_P$3") (pintype "passive"))
      (node (ref "FS11") (pin "P$4") (pinfunction "2_P$4") (pintype "passive"))
      (node (ref "FS12") (pin "P$3") (pinfunction "2_P$3") (pintype "passive"))
      (node (ref "FS12") (pin "P$4") (pinfunction "2_P$4") (pintype "passive"))
      (node (ref "FS13") (pin "P$3") (pinfunction "2_P$3") (pintype "passive"))
      (node (ref "FS13") (pin "P$4") (pinfunction "2_P$4") (pintype "passive"))
      (node (ref "FS14") (pin "P$3") (pinfunction "2_P$3") (pintype "passive"))
      (node (ref "FS14") (pin "P$4") (pinfunction "2_P$4") (pintype "passive"))
      (node (ref "IC5") (pin "4") (pinfunction "V+_4") (pintype "power_in"))
      (node (ref "IC6") (pin "4") (pinfunction "V+_4") (pintype "power_in"))
      (node (ref "JP8") (pin "2") (pinfunction "2_2") (pintype "passive"))
      (node (ref "PWR_10V") (pin "A") (pinfunction "A_A") (pintype "passive"))
      (node (ref "R1") (pin "2") (pinfunction "2_2") (pintype "passive"))
      (node (ref "VR3") (pin "P$2") (pinfunction "VO_P$2") (pintype "bidirectional"))
      (node (ref "VR3") (pin "P$4") (pinfunction "VO_P$4") (pintype "bidirectional"))
      (node (ref "VR3") (pin "P$5") (pinfunction "VO_P$5") (pintype "bidirectional"))
    )
    (net (code "3") (name "+12V") (class "Default")
      (node (ref "C4") (pin "1") (pinfunction "1_1") (pintype "passive"))
      (node (ref "C6") (pin "1") (pinfunction "1_1") (pintype "passive"))
      (node (ref "CON_12V") (pin "1") (pinfunction "SK_1") (pintype "passive"))
      (node (ref "CON_12V") (pin "2") (pinfunction "SK_2") (pintype "passive"))
      (node (ref "CON_ROUTER") (pin "1") (pinfunction "SK_1") (pintype "passive"))
      (node (ref "CON_ROUTER") (pin "2") (pinfunction "SK_2") (pintype "passive"))
      (node (ref "D2") (pin "P$1") (pinfunction "P$1_P$1") (pintype "bidirectional"))
      (node (ref "D3") (pin "P$1") (pinfunction "P$1_P$1") (pintype "bidirectional"))
      (node (ref "D4") (pin "C") (pinfunction "C_C") (pintype "passive"))
      (node (ref "FS1") (pin "P$3") (pinfunction "2_P$3") (pintype "passive"))
      (node (ref "FS1") (pin "P$4") (pinfunction "2_P$4") (pintype "passive"))
      (node (ref "FS2") (pin "P$3") (pinfunction "2_P$3") (pintype "passive"))
      (node (ref "FS2") (pin "P$4") (pinfunction "2_P$4") (pintype "passive"))
      (node (ref "FS3") (pin "P$3") (pinfunction "2_P$3") (pintype "passive"))
      (node (ref "FS3") (pin "P$4") (pinfunction "2_P$4") (pintype "passive"))
      (node (ref "FS4") (pin "P$3") (pinfunction "2_P$3") (pintype "passive"))
      (node (ref "FS4") (pin "P$4") (pinfunction "2_P$4") (pintype "passive"))
      (node (ref "FS5") (pin "P$3") (pinfunction "2_P$3") (pintype "passive"))
      (node (ref "FS5") (pin "P$4") (pinfunction "2_P$4") (pintype "passive"))
      (node (ref "FS6") (pin "P$3") (pinfunction "2_P$3") (pintype "passive"))
      (node (ref "FS6") (pin "P$4") (pinfunction "2_P$4") (pintype "passive"))
      (node (ref "PWR_12V") (pin "A") (pinfunction "A_A") (pintype "passive"))
      (node (ref "SW2") (pin "2") (pinfunction "P_2") (pintype "passive"))
      (node (ref "VR2") (pin "P$3") (pinfunction "VIN_P$3") (pintype "bidirectional"))
      (node (ref "VR3") (pin "P$3") (pinfunction "VIN_P$3") (pintype "bidirectional"))
    )
    (net (code "4") (name "10V_FB") (class "Default")
      (node (ref "R1") (pin "1") (pinfunction "1_1") (pintype "passive"))
      (node (ref "R2") (pin "2") (pinfunction "2_2") (pintype "passive"))
      (node (ref "VR3") (pin "P$1") (pinfunction "ADJ_P$1") (pintype "bidirectional"))
    )
    (net (code "5") (name "12V_CON") (class "Default")
      (node (ref "CON_BATTERY") (pin "1") (pinfunction "SK_1") (pintype "passive"))
      (node (ref "CON_BATTERY") (pin "2") (pinfunction "SK_2") (pintype "passive"))
      (node (ref "SW1") (pin "2") (pinfunction "P_2") (pintype "passive"))
    )
    (net (code "6") (name "12V_IN") (class "Default")
      (node (ref "D4") (pin "A") (pinfunction "A_A") (pintype "passive"))
      (node (ref "SW1") (pin "1") (pinfunction "O_1") (pintype "passive"))
    )
    (net (code "7") (name "ADC1_CS") (class "Default")
      (node (ref "ADC1") (pin "10") (pinfunction "CS*_10") (pintype "bidirectional"))
      (node (ref "R74") (pin "1") (pinfunction "1_1") (pintype "passive"))
      (node (ref "X1") (pin "22") (pinfunction "KL_22") (pintype "passive"))
    )
    (net (code "8") (name "ADC2_CS") (class "Default")
      (node (ref "ADC2") (pin "10") (pinfunction "CS*_10") (pintype "bidirectional"))
      (node (ref "R75") (pin "1") (pinfunction "1_1") (pintype "passive"))
      (node (ref "X1") (pin "24") (pinfunction "KL_24") (pintype "passive"))
    )
    (net (code "9") (name "ADC3_CS") (class "Default")
      (node (ref "ADC3") (pin "10") (pinfunction "CS*_10") (pintype "bidirectional"))
      (node (ref "R76") (pin "1") (pinfunction "1_1") (pintype "passive"))
      (node (ref "X1") (pin "26") (pinfunction "KL_26") (pintype "passive"))
    )
    (net (code "10") (name "DRV_CTL_1") (class "Default")
      (node (ref "JP7") (pin "1") (pinfunction "1_1") (pintype "passive"))
      (node (ref "R3") (pin "1") (pinfunction "1_1") (pintype "passive"))
      (node (ref "R7") (pin "2") (pinfunction "2_2") (pintype "passive"))
      (node (ref "T1") (pin "1") (pinfunction "G_1") (pintype "passive"))
      (node (ref "X1") (pin "11") (pinfunction "KL_11") (pintype "passive"))
    )
    (net (code "11") (name "DRV_CTL_2") (class "Default")
      (node (ref "JP7") (pin "2") (pinfunction "2_2") (pintype "passive"))
      (node (ref "R10") (pin "2") (pinfunction "2_2") (pintype "passive"))
      (node (ref "R41") (pin "1") (pinfunction "1_1") (pintype "passive"))
      (node (ref "T2") (pin "1") (pinfunction "G_1") (pintype "passive"))
      (node (ref "X1") (pin "13") (pinfunction "KL_13") (pintype "passive"))
    )
    (net (code "12") (name "DRV_CTL_3") (class "Default")
      (node (ref "JP7") (pin "3") (pinfunction "3_3") (pintype "passive"))
      (node (ref "R13") (pin "2") (pinfunction "2_2") (pintype "passive"))
      (node (ref "R42") (pin "1") (pinfunction "1_1") (pintype "passive"))
      (node (ref "T3") (pin "1") (pinfunction "G_1") (pintype "passive"))
      (node (ref "X1") (pin "15") (pinfunction "KL_15") (pintype "passive"))
    )
    (net (code "13") (name "DRV_CTL_4") (class "Default")
      (node (ref "JP7") (pin "4") (pinfunction "4_4") (pintype "passive"))
      (node (ref "R16") (pin "2") (pinfunction "2_2") (pintype "passive"))
      (node (ref "R43") (pin "1") (pinfunction "1_1") (pintype "passive"))
      (node (ref "T4") (pin "1") (pinfunction "G_1") (pintype "passive"))
      (node (ref "X1") (pin "18") (pinfunction "KL_18") (pintype "passive"))
    )
    (net (code "14") (name "DRV_CTL_5") (class "Default")
      (node (ref "JP7") (pin "5") (pinfunction "5_5") (pintype "passive"))
      (node (ref "R19") (pin "2") (pinfunction "2_2") (pintype "passive"))
      (node (ref "R44") (pin "1") (pinfunction "1_1") (pintype "passive"))
      (node (ref "T5") (pin "1") (pinfunction "G_1") (pintype "passive"))
      (node (ref "X1") (pin "33") (pinfunction "KL_33") (pintype "passive"))
    )
    (net (code "15") (name "DRV_CTL_6") (class "Default")
      (node (ref "JP7") (pin "6") (pinfunction "6_6") (pintype "passive"))
      (node (ref "R22") (pin "2") (pinfunction "2_2") (pintype "passive"))
      (node (ref "R45") (pin "1") (pinfunction "1_1") (pintype "passive"))
      (node (ref "T6") (pin "1") (pinfunction "G_1") (pintype "passive"))
      (node (ref "X1") (pin "32") (pinfunction "KL_32") (pintype "passive"))
    )
    (net (code "16") (name "DRV_NEG_1") (class "Default")
      (node (ref "CON_DRV1") (pin "3") (pinfunction "SK_3") (pintype "passive"))
      (node (ref "CON_DRV1") (pin "4") (pinfunction "SK_4") (pintype "passive"))
      (node (ref "D5") (pin "P$2") (pinfunction "P$2_P$2") (pintype "bidirectional"))
      (node (ref "R9") (pin "1") (pinfunction "1_1") (pintype "passive"))
      (node (ref "T1") (pin "2") (pinfunction "D_2") (pintype "passive"))
    )
    (net (code "17") (name "DRV_NEG_2") (class "Default")
      (node (ref "CON_DRV2") (pin "3") (pinfunction "SK_3") (pintype "passive"))
      (node (ref "CON_DRV2") (pin "4") (pinfunction "SK_4") (pintype "passive"))
      (node (ref "D6") (pin "P$2") (pinfunction "P$2_P$2") (pintype "bidirectional"))
      (node (ref "R12") (pin "1") (pinfunction "1_1") (pintype "passive"))
      (node (ref "T2") (pin "2") (pinfunction "D_2") (pintype "passive"))
    )
    (net (code "18") (name "DRV_NEG_3") (class "Default")
      (node (ref "CON_DRV3") (pin "3") (pinfunction "SK_3") (pintype "passive"))
      (node (ref "CON_DRV3") (pin "4") (pinfunction "SK_4") (pintype "passive"))
      (node (ref "D7") (pin "P$2") (pinfunction "P$2_P$2") (pintype "bidirectional"))
      (node (ref "R15") (pin "1") (pinfunction "1_1") (pintype "passive"))
      (node (ref "T3") (pin "2") (pinfunction "D_2") (pintype "passive"))
    )
    (net (code "19") (name "DRV_NEG_4") (class "Default")
      (node (ref "CON_DRV4") (pin "3") (pinfunction "SK_3") (pintype "passive"))
      (node (ref "CON_DRV4") (pin "4") (pinfunction "SK_4") (pintype "passive"))
      (node (ref "D8") (pin "P$2") (pinfunction "P$2_P$2") (pintype "bidirectional"))
      (node (ref "R18") (pin "1") (pinfunction "1_1") (pintype "passive"))
      (node (ref "T4") (pin "2") (pinfunction "D_2") (pintype "passive"))
    )
    (net (code "20") (name "DRV_NEG_5") (class "Default")
      (node (ref "CON_DRV5") (pin "3") (pinfunction "SK_3") (pintype "passive"))
      (node (ref "CON_DRV5") (pin "4") (pinfunction "SK_4") (pintype "passive"))
      (node (ref "D9") (pin "P$2") (pinfunction "P$2_P$2") (pintype "bidirectional"))
      (node (ref "R21") (pin "1") (pinfunction "1_1") (pintype "passive"))
      (node (ref "T5") (pin "2") (pinfunction "D_2") (pintype "passive"))
    )
    (net (code "21") (name "DRV_NEG_6") (class "Default")
      (node (ref "CON_DRV6") (pin "3") (pinfunction "SK_3") (pintype "passive"))
      (node (ref "CON_DRV6") (pin "4") (pinfunction "SK_4") (pintype "passive"))
      (node (ref "D10") (pin "P$2") (pinfunction "P$2_P$2") (pintype "bidirectional"))
      (node (ref "R24") (pin "1") (pinfunction "1_1") (pintype "passive"))
      (node (ref "T6") (pin "2") (pinfunction "D_2") (pintype "passive"))
    )
    (net (code "22") (name "DRV_POS_1") (class "Default")
      (node (ref "CON_DRV1") (pin "1") (pinfunction "SK_1") (pintype "passive"))
      (node (ref "CON_DRV1") (pin "2") (pinfunction "SK_2") (pintype "passive"))
      (node (ref "D5") (pin "P$1") (pinfunction "P$1_P$1") (pintype "bidirectional"))
      (node (ref "DRV_STAT_1") (pin "A") (pinfunction "A_A") (pintype "passive"))
      (node (ref "FS1") (pin "P$1") (pinfunction "1_P$1") (pintype "passive"))
      (node (ref "FS1") (pin "P$2") (pinfunction "1_P$2") (pintype "passive"))
      (node (ref "FS_STAT_1") (pin "A") (pinfunction "A_A") (pintype "passive"))
    )
    (net (code "23") (name "DRV_POS_2") (class "Default")
      (node (ref "CON_DRV2") (pin "1") (pinfunction "SK_1") (pintype "passive"))
      (node (ref "CON_DRV2") (pin "2") (pinfunction "SK_2") (pintype "passive"))
      (node (ref "D6") (pin "P$1") (pinfunction "P$1_P$1") (pintype "bidirectional"))
      (node (ref "DRV_STAT_2") (pin "A") (pinfunction "A_A") (pintype "passive"))
      (node (ref "FS2") (pin "P$1") (pinfunction "1_P$1") (pintype "passive"))
      (node (ref "FS2") (pin "P$2") (pinfunction "1_P$2") (pintype "passive"))
      (node (ref "FS_STAT_2") (pin "A") (pinfunction "A_A") (pintype "passive"))
    )
    (net (code "24") (name "DRV_POS_3") (class "Default")
      (node (ref "CON_DRV3") (pin "1") (pinfunction "SK_1") (pintype "passive"))
      (node (ref "CON_DRV3") (pin "2") (pinfunction "SK_2") (pintype "passive"))
      (node (ref "D7") (pin "P$1") (pinfunction "P$1_P$1") (pintype "bidirectional"))
      (node (ref "DRV_STAT_3") (pin "A") (pinfunction "A_A") (pintype "passive"))
      (node (ref "FS3") (pin "P$1") (pinfunction "1_P$1") (pintype "passive"))
      (node (ref "FS3") (pin "P$2") (pinfunction "1_P$2") (pintype "passive"))
      (node (ref "FS_STAT_3") (pin "A") (pinfunction "A_A") (pintype "passive"))
    )
    (net (code "25") (name "DRV_POS_4") (class "Default")
      (node (ref "CON_DRV4") (pin "1") (pinfunction "SK_1") (pintype "passive"))
      (node (ref "CON_DRV4") (pin "2") (pinfunction "SK_2") (pintype "passive"))
      (node (ref "D8") (pin "P$1") (pinfunction "P$1_P$1") (pintype "bidirectional"))
      (node (ref "DRV_STAT_4") (pin "A") (pinfunction "A_A") (pintype "passive"))
      (node (ref "FS4") (pin "P$1") (pinfunction "1_P$1") (pintype "passive"))
      (node (ref "FS4") (pin "P$2") (pinfunction "1_P$2") (pintype "passive"))
      (node (ref "FS_STAT_4") (pin "A") (pinfunction "A_A") (pintype "passive"))
    )
    (net (code "26") (name "DRV_POS_5") (class "Default")
      (node (ref "CON_DRV5") (pin "1") (pinfunction "SK_1") (pintype "passive"))
      (node (ref "CON_DRV5") (pin "2") (pinfunction "SK_2") (pintype "passive"))
      (node (ref "D9") (pin "P$1") (pinfunction "P$1_P$1") (pintype "bidirectional"))
      (node (ref "DRV_STAT_5") (pin "A") (pinfunction "A_A") (pintype "passive"))
      (node (ref "FS5") (pin "P$1") (pinfunction "1_P$1") (pintype "passive"))
      (node (ref "FS5") (pin "P$2") (pinfunction "1_P$2") (pintype "passive"))
      (node (ref "FS_STAT_5") (pin "A") (pinfunction "A_A") (pintype "passive"))
    )
    (net (code "27") (name "DRV_POS_6") (class "Default")
      (node (ref "CON_DRV6") (pin "1") (pinfunction "SK_1") (pintype "passive"))
      (node (ref "CON_DRV6") (pin "2") (pinfunction "SK_2") (pintype "passive"))
      (node (ref "D10") (pin "P$1") (pinfunction "P$1_P$1") (pintype "bidirectional"))
      (node (ref "DRV_STAT_6") (pin "A") (pinfunction "A_A") (pintype "passive"))
      (node (ref "FS6") (pin "P$1") (pinfunction "1_P$1") (pintype "passive"))
      (node (ref "FS6") (pin "P$2") (pinfunction "1_P$2") (pintype "passive"))
      (node (ref "FS_STAT_6") (pin "A") (pinfunction "A_A") (pintype "passive"))
    )
    (net (code "28") (name "GND") (class "Default")
      (node (ref "ADC1") (pin "14") (pinfunction "AGND_14") (pintype "bidirectional"))
      (node (ref "ADC1") (pin "9") (pinfunction "DGND_9") (pintype "bidirectional"))
      (node (ref "ADC2") (pin "14") (pinfunction "AGND_14") (pintype "bidirectional"))
      (node (ref "ADC2") (pin "9") (pinfunction "DGND_9") (pintype "bidirectional"))
      (node (ref "ADC3") (pin "14") (pinfunction "AGND_14") (pintype "bidirectional"))
      (node (ref "ADC3") (pin "9") (pinfunction "DGND_9") (pintype "bidirectional"))
      (node (ref "C1") (pin "2") (pinfunction "2_2") (pintype "passive"))
      (node (ref "C10") (pin "2") (pinfunction "2_2") (pintype "passive"))
      (node (ref "C11") (pin "2") (pinfunction "2_2") (pintype "passive"))
      (node (ref "C13") (pin "2") (pinfunction "2_2") (pintype "passive"))
      (node (ref "C15") (pin "2") (pinfunction "2_2") (pintype "passive"))
      (node (ref "C17") (pin "2") (pinfunction "2_2") (pintype "passive"))
      (node (ref "C19") (pin "2") (pinfunction "2_2") (pintype "passive"))
      (node (ref "C20") (pin "2") (pinfunction "2_2") (pintype "passive"))
      (node (ref "C21") (pin "2") (pinfunction "2_2") (pintype "passive"))
      (node (ref "C23") (pin "2") (pinfunction "2_2") (pintype "passive"))
      (node (ref "C25") (pin "2") (pinfunction "2_2") (pintype "passive"))
      (node (ref "C27") (pin "2") (pinfunction "2_2") (pintype "passive"))
      (node (ref "C28") (pin "2") (pinfunction "2_2") (pintype "passive"))
      (node (ref "C29") (pin "2") (pinfunction "2_2") (pintype "passive"))
      (node (ref "C3") (pin "2") (pinfunction "2_2") (pintype "passive"))
      (node (ref "C4") (pin "2") (pinfunction "2_2") (pintype "passive"))
      (node (ref "C5") (pin "2") (pinfunction "2_2") (pintype "passive"))
      (node (ref "C6") (pin "2") (pinfunction "2_2") (pintype "passive"))
      (node (ref "C7") (pin "2") (pinfunction "2_2") (pintype "passive"))
      (node (ref "C8") (pin "2") (pinfunction "2_2") (pintype "passive"))
      (node (ref "C9") (pin "2") (pinfunction "2_2") (pintype "passive"))
      (node (ref "CON_12V") (pin "3") (pinfunction "SK_3") (pintype "passive"))
      (node (ref "CON_12V") (pin "4") (pinfunction "SK_4") (pintype "passive"))
      (node (ref "CON_BATTERY") (pin "3") (pinfunction "SK_3") (pintype "passive"))
      (node (ref "CON_BATTERY") (pin "4") (pinfunction "SK_4") (pintype "passive"))
      (node (ref "CON_FAN") (pin "3") (pinfunction "SK_3") (pintype "passive"))
      (node (ref "CON_FAN") (pin "4") (pinfunction "SK_4") (pintype "passive"))
      (node (ref "CON_LC1") (pin "7") (pinfunction "SK_7") (pintype "passive"))
      (node (ref "CON_LC1") (pin "8") (pinfunction "SK_8") (pintype "passive"))
      (node (ref "CON_LC2") (pin "7") (pinfunction "SK_7") (pintype "passive"))
      (node (ref "CON_LC2") (pin "8") (pinfunction "SK_8") (pintype "passive"))
      (node (ref "CON_LC3") (pin "7") (pinfunction "SK_7") (pintype "passive"))
      (node (ref "CON_LC3") (pin "8") (pinfunction "SK_8") (pintype "passive"))
      (node (ref "CON_LC4") (pin "7") (pinfunction "SK_7") (pintype "passive"))
      (node (ref "CON_LC4") (pin "8") (pinfunction "SK_8") (pintype "passive"))
      (node (ref "CON_ROUTER") (pin "3") (pinfunction "SK_3") (pintype "passive"))
      (node (ref "CON_ROUTER") (pin "4") (pinfunction "SK_4") (pintype "passive"))
      (node (ref "CON_TC1") (pin "5") (pinfunction "SK_5") (pintype "passive"))
      (node (ref "CON_TC1") (pin "6") (pinfunction "SK_6") (pintype "passive"))
      (node (ref "CON_TC2") (pin "5") (pinfunction "SK_5") (pintype "passive"))
      (node (ref "CON_TC2") (pin "6") (pinfunction "SK_6") (pintype "passive"))
      (node (ref "CON_TC3") (pin "5") (pinfunction "SK_5") (pintype "passive"))
      (node (ref "CON_TC3") (pin "6") (pinfunction "SK_6") (pintype "passive"))
      (node (ref "CON_TC4") (pin "5") (pinfunction "SK_5") (pintype "passive"))
      (node (ref "CON_TC4") (pin "6") (pinfunction "SK_6") (pintype "passive"))
      (node (ref "IC1") (pin "4") (pinfunction "-V_4") (pintype "power_in"))
      (node (ref "IC2") (pin "4") (pinfunction "-V_4") (pintype "power_in"))
      (node (ref "IC3") (pin "4") (pinfunction "-V_4") (pintype "power_in"))
      (node (ref "IC4") (pin "4") (pinfunction "-V_4") (pintype "power_in"))
      (node (ref "IC5") (pin "11") (pinfunction "V-_11") (pintype "power_in"))
      (node (ref "IC6") (pin "11") (pinfunction "V-_11") (pintype "power_in"))
      (node (ref "JP8") (pin "4") (pinfunction "4_4") (pintype "passive"))
      (node (ref "R10") (pin "1") (pinfunction "1_1") (pintype "passive"))
      (node (ref "R11") (pin "1") (pinfunction "1_1") (pintype "passive"))
      (node (ref "R13") (pin "1") (pinfunction "1_1") (pintype "passive"))
      (node (ref "R14") (pin "1") (pinfunction "1_1") (pintype "passive"))
      (node (ref "R16") (pin "1") (pinfunction "1_1") (pintype "passive"))
      (node (ref "R17") (pin "1") (pinfunction "1_1") (pintype "passive"))
      (node (ref "R19") (pin "1") (pinfunction "1_1") (pintype "passive"))
      (node (ref "R2") (pin "1") (pinfunction "1_1") (pintype "passive"))
      (node (ref "R20") (pin "1") (pinfunction "1_1") (pintype "passive"))
      (node (ref "R22") (pin "1") (pinfunction "1_1") (pintype "passive"))
      (node (ref "R23") (pin "1") (pinfunction "1_1") (pintype "passive"))
      (node (ref "R26") (pin "1") (pinfunction "1_1") (pintype "passive"))
      (node (ref "R30") (pin "1") (pinfunction "1_1") (pintype "passive"))
      (node (ref "R34") (pin "1") (pinfunction "1_1") (pintype "passive"))
      (node (ref "R38") (pin "1") (pinfunction "1_1") (pintype "passive"))
      (node (ref "R4") (pin "1") (pinfunction "1_1") (pintype "passive"))
      (node (ref "R46") (pin "A") (pinfunction "A_A") (pintype "passive"))
      (node (ref "R47") (pin "A") (pinfunction "A_A") (pintype "passive"))
      (node (ref "R48") (pin "A") (pinfunction "A_A") (pintype "passive"))
      (node (ref "R5") (pin "1") (pinfunction "1_1") (pintype "passive"))
      (node (ref "R54") (pin "1") (pinfunction "1_1") (pintype "passive"))
      (node (ref "R57") (pin "1") (pinfunction "1_1") (pintype "passive"))
      (node (ref "R6") (pin "1") (pinfunction "1_1") (pintype "passive"))
      (node (ref "R60") (pin "1") (pinfunction "1_1") (pintype "passive"))
      (node (ref "R63") (pin "1") (pinfunction "1_1") (pintype "passive"))
      (node (ref "R67") (pin "1") (pinfunction "1_1") (pintype "passive"))
      (node (ref "R69") (pin "1") (pinfunction "1_1") (pintype "passive"))
      (node (ref "R7") (pin "1") (pinfunction "1_1") (pintype "passive"))
      (node (ref "R71") (pin "1") (pinfunction "1_1") (pintype "passive"))
      (node (ref "R73") (pin "1") (pinfunction "1_1") (pintype "passive"))
      (node (ref "R77") (pin "1") (pinfunction "1_1") (pintype "passive"))
      (node (ref "R78") (pin "A") (pinfunction "A_A") (pintype "passive"))
      (node (ref "R8") (pin "1") (pinfunction "1_1") (pintype "passive"))
      (node (ref "T1") (pin "3") (pinfunction "S_3") (pintype "passive"))
      (node (ref "T2") (pin "3") (pinfunction "S_3") (pintype "passive"))
      (node (ref "T3") (pin "3") (pinfunction "S_3") (pintype "passive"))
      (node (ref "T4") (pin "3") (pinfunction "S_3") (pintype "passive"))
      (node (ref "T5") (pin "3") (pinfunction "S_3") (pintype "passive"))
      (node (ref "T6") (pin "3") (pinfunction "S_3") (pintype "passive"))
      (node (ref "VR2") (pin "P$1") (pinfunction "GND_P$1") (pintype "bidirectional"))
      (node (ref "X1") (pin "14") (pinfunction "KL_14") (pintype "passive"))
      (node (ref "X1") (pin "20") (pinfunction "KL_20") (pintype "passive"))
      (node (ref "X1") (pin "25") (pinfunction "KL_25") (pintype "passive"))
      (node (ref "X1") (pin "30") (pinfunction "KL_30") (pintype "passive"))
      (node (ref "X1") (pin "34") (pinfunction "KL_34") (pintype "passive"))
      (node (ref "X1") (pin "39") (pinfunction "KL_39") (pintype "passive"))
      (node (ref "X1") (pin "6") (pinfunction "KL_6") (pintype "passive"))
      (node (ref "X1") (pin "9") (pinfunction "KL_9") (pintype "passive"))
    )
    (net (code "29") (name "HBT") (class "Default")
      (node (ref "HBT") (pin "A") (pinfunction "A_A") (pintype "passive"))
      (node (ref "X1") (pin "29") (pinfunction "KL_29") (pintype "passive"))
    )
    (net (code "30") (name "LC1+") (class "Default")
      (node (ref "CON_LC1") (pin "3") (pinfunction "SK_3") (pintype "passive"))
      (node (ref "CON_LC1") (pin "4") (pinfunction "SK_4") (pintype "passive"))
      (node (ref "IC1") (pin "3") (pinfunction "+_3") (pintype "input"))
      (node (ref "JP5") (pin "1") (pinfunction "1_1") (pintype "passive"))
    )
    (net (code "31") (name "LC1-") (class "Default")
      (node (ref "CON_LC1") (pin "5") (pinfunction "SK_5") (pintype "passive"))
      (node (ref "CON_LC1") (pin "6") (pinfunction "SK_6") (pintype "passive"))
      (node (ref "IC1") (pin "2") (pinfunction "-_2") (pintype "input"))
      (node (ref "JP5") (pin "2") (pinfunction "2_2") (pintype "passive"))
    )
    (net (code "32") (name "LC1_CAL") (class "Default")
      (node (ref "ADC1") (pin "1") (pinfunction "CH0_1") (pintype "bidirectional"))
      (node (ref "C12") (pin "2") (pinfunction "2_2") (pintype "passive"))
      (node (ref "IC5") (pin "1") (pinfunction "OUT_1") (pintype "output"))
      (node (ref "JP2") (pin "1") (pinfunction "1_1") (pintype "passive"))
      (node (ref "R25") (pin "2") (pinfunction "2_2") (pintype "passive"))
    )
    (net (code "33") (name "LC1_PREC") (class "Default")
      (node (ref "IC1") (pin "6") (pinfunction "OUT_6") (pintype "output"))
      (node (ref "JP6") (pin "1") (pinfunction "1_1") (pintype "passive"))
      (node (ref "R28") (pin "1") (pinfunction "1_1") (pintype "passive"))
      (node (ref "RF1") (pin "1") (pinfunction "1_1") (pintype "passive"))
      (node (ref "RG1") (pin "2") (pinfunction "2_2") (pintype "passive"))
    )
    (net (code "34") (name "LC2+") (class "Default")
      (node (ref "CON_LC2") (pin "3") (pinfunction "SK_3") (pintype "passive"))
      (node (ref "CON_LC2") (pin "4") (pinfunction "SK_4") (pintype "passive"))
      (node (ref "IC2") (pin "3") (pinfunction "+_3") (pintype "input"))
      (node (ref "JP5") (pin "3") (pinfunction "3_3") (pintype "passive"))
    )
    (net (code "35") (name "LC2-") (class "Default")
      (node (ref "CON_LC2") (pin "5") (pinfunction "SK_5") (pintype "passive"))
      (node (ref "CON_LC2") (pin "6") (pinfunction "SK_6") (pintype "passive"))
      (node (ref "IC2") (pin "2") (pinfunction "-_2") (pintype "input"))
      (node (ref "JP5") (pin "4") (pinfunction "4_4") (pintype "passive"))
    )
    (net (code "36") (name "LC2_CAL") (class "Default")
      (node (ref "ADC1") (pin "2") (pinfunction "CH1_2") (pintype "bidirectional"))
      (node (ref "C14") (pin "2") (pinfunction "2_2") (pintype "passive"))
      (node (ref "IC5") (pin "7") (pinfunction "OUT_7") (pintype "output"))
      (node (ref "JP2") (pin "2") (pinfunction "2_2") (pintype "passive"))
      (node (ref "R29") (pin "2") (pinfunction "2_2") (pintype "passive"))
    )
    (net (code "37") (name "LC2_PREC") (class "Default")
      (node (ref "IC2") (pin "6") (pinfunction "OUT_6") (pintype "output"))
      (node (ref "JP6") (pin "2") (pinfunction "2_2") (pintype "passive"))
      (node (ref "R32") (pin "1") (pinfunction "1_1") (pintype "passive"))
      (node (ref "RF2") (pin "1") (pinfunction "1_1") (pintype "passive"))
      (node (ref "RG2") (pin "2") (pinfunction "2_2") (pintype "passive"))
    )
    (net (code "38") (name "LC3+") (class "Default")
      (node (ref "CON_LC3") (pin "3") (pinfunction "SK_3") (pintype "passive"))
      (node (ref "CON_LC3") (pin "4") (pinfunction "SK_4") (pintype "passive"))
      (node (ref "IC3") (pin "3") (pinfunction "+_3") (pintype "input"))
      (node (ref "JP5") (pin "5") (pinfunction "5_5") (pintype "passive"))
    )
    (net (code "39") (name "LC3-") (class "Default")
      (node (ref "CON_LC3") (pin "5") (pinfunction "SK_5") (pintype "passive"))
      (node (ref "CON_LC3") (pin "6") (pinfunction "SK_6") (pintype "passive"))
      (node (ref "IC3") (pin "2") (pinfunction "-_2") (pintype "input"))
      (node (ref "JP5") (pin "6") (pinfunction "6_6") (pintype "passive"))
    )
    (net (code "40") (name "LC3_CAL") (class "Default")
      (node (ref "ADC1") (pin "3") (pinfunction "CH2_3") (pintype "bidirectional"))
      (node (ref "C16") (pin "2") (pinfunction "2_2") (pintype "passive"))
      (node (ref "IC5") (pin "8") (pinfunction "OUT_8") (pintype "output"))
      (node (ref "JP2") (pin "3") (pinfunction "3_3") (pintype "passive"))
      (node (ref "R33") (pin "2") (pinfunction "2_2") (pintype "passive"))
    )
    (net (code "41") (name "LC3_PREC") (class "Default")
      (node (ref "IC3") (pin "6") (pinfunction "OUT_6") (pintype "output"))
      (node (ref "JP6") (pin "3") (pinfunction "3_3") (pintype "passive"))
      (node (ref "R36") (pin "1") (pinfunction "1_1") (pintype "passive"))
      (node (ref "RF3") (pin "1") (pinfunction "1_1") (pintype "passive"))
      (node (ref "RG3") (pin "2") (pinfunction "2_2") (pintype "passive"))
    )
    (net (code "42") (name "LC4+") (class "Default")
      (node (ref "CON_LC4") (pin "3") (pinfunction "SK_3") (pintype "passive"))
      (node (ref "CON_LC4") (pin "4") (pinfunction "SK_4") (pintype "passive"))
      (node (ref "IC4") (pin "3") (pinfunction "+_3") (pintype "input"))
      (node (ref "JP5") (pin "7") (pinfunction "7_7") (pintype "passive"))
    )
    (net (code "43") (name "LC4-") (class "Default")
      (node (ref "CON_LC4") (pin "5") (pinfunction "SK_5") (pintype "passive"))
      (node (ref "CON_LC4") (pin "6") (pinfunction "SK_6") (pintype "passive"))
      (node (ref "IC4") (pin "2") (pinfunction "-_2") (pintype "input"))
      (node (ref "JP5") (pin "8") (pinfunction "8_8") (pintype "passive"))
    )
    (net (code "44") (name "LC4_CAL") (class "Default")
      (node (ref "ADC1") (pin "4") (pinfunction "CH3_4") (pintype "bidirectional"))
      (node (ref "C18") (pin "2") (pinfunction "2_2") (pintype "passive"))
      (node (ref "IC5") (pin "14") (pinfunction "OUT_14") (pintype "output"))
      (node (ref "JP2") (pin "4") (pinfunction "4_4") (pintype "passive"))
      (node (ref "R37") (pin "2") (pinfunction "2_2") (pintype "passive"))
    )
    (net (code "45") (name "LC4_PREC") (class "Default")
      (node (ref "IC4") (pin "6") (pinfunction "OUT_6") (pintype "output"))
      (node (ref "JP6") (pin "4") (pinfunction "4_4") (pintype "passive"))
      (node (ref "R40") (pin "1") (pinfunction "1_1") (pintype "passive"))
      (node (ref "RF4") (pin "1") (pinfunction "1_1") (pintype "passive"))
      (node (ref "RG4") (pin "2") (pinfunction "2_2") (pintype "passive"))
    )
    (net (code "46") (name "Net-(ADC1-CH4)") (class "Default")
      (node (ref "ADC1") (pin "5") (pinfunction "CH4_5") (pintype "bidirectional"))
      (node (ref "JP2") (pin "5") (pinfunction "5_5") (pintype "passive"))
    )
    (net (code "47") (name "Net-(ADC1-CH5)") (class "Default")
      (node (ref "ADC1") (pin "6") (pinfunction "CH5_6") (pintype "bidirectional"))
      (node (ref "JP2") (pin "6") (pinfunction "6_6") (pintype "passive"))
    )
    (net (code "48") (name "Net-(ADC1-CH6)") (class "Default")
      (node (ref "ADC1") (pin "7") (pinfunction "CH6_7") (pintype "bidirectional"))
      (node (ref "JP2") (pin "7") (pinfunction "7_7") (pintype "passive"))
    )
    (net (code "49") (name "Net-(ADC1-CH7)") (class "Default")
      (node (ref "ADC1") (pin "8") (pinfunction "CH7_8") (pintype "bidirectional"))
      (node (ref "JP2") (pin "8") (pinfunction "8_8") (pintype "passive"))
    )
    (net (code "50") (name "Net-(ADC2-CH4)") (class "Default")
      (node (ref "ADC2") (pin "5") (pinfunction "CH4_5") (pintype "bidirectional"))
      (node (ref "JP3") (pin "5") (pinfunction "5_5") (pintype "passive"))
    )
    (net (code "51") (name "Net-(ADC2-CH5)") (class "Default")
      (node (ref "ADC2") (pin "6") (pinfunction "CH5_6") (pintype "bidirectional"))
      (node (ref "JP3") (pin "6") (pinfunction "6_6") (pintype "passive"))
    )
    (net (code "52") (name "Net-(ADC2-CH6)") (class "Default")
      (node (ref "ADC2") (pin "7") (pinfunction "CH6_7") (pintype "bidirectional"))
      (node (ref "JP3") (pin "7") (pinfunction "7_7") (pintype "passive"))
    )
    (net (code "53") (name "Net-(ADC2-CH7)") (class "Default")
      (node (ref "ADC2") (pin "8") (pinfunction "CH7_8") (pintype "bidirectional"))
      (node (ref "JP3") (pin "8") (pinfunction "8_8") (pintype "passive"))
    )
    (net (code "54") (name "Net-(ADC3-CH4)") (class "Default")
      (node (ref "ADC3") (pin "5") (pinfunction "CH4_5") (pintype "bidirectional"))
      (node (ref "JP1") (pin "5") (pinfunction "5_5") (pintype "passive"))
    )
    (net (code "55") (name "Net-(ADC3-CH5)") (class "Default")
      (node (ref "ADC3") (pin "6") (pinfunction "CH5_6") (pintype "bidirectional"))
      (node (ref "JP1") (pin "6") (pinfunction "6_6") (pintype "passive"))
    )
    (net (code "56") (name "Net-(ADC3-CH6)") (class "Default")
      (node (ref "ADC3") (pin "7") (pinfunction "CH6_7") (pintype "bidirectional"))
      (node (ref "JP1") (pin "7") (pinfunction "7_7") (pintype "passive"))
    )
    (net (code "57") (name "Net-(ADC3-CH7)") (class "Default")
      (node (ref "ADC3") (pin "8") (pinfunction "CH7_8") (pintype "bidirectional"))
      (node (ref "JP1") (pin "8") (pinfunction "8_8") (pintype "passive"))
    )
    (net (code "58") (name "Net-(C2-Pad1)") (class "Default")
      (node (ref "C2") (pin "1") (pinfunction "1_1") (pintype "passive"))
      (node (ref "R55") (pin "2") (pinfunction "2_2") (pintype "passive"))
      (node (ref "R56") (pin "1") (pinfunction "1_1") (pintype "passive"))
    )
    (net (code "59") (name "Net-(C12-Pad1)") (class "Default")
      (node (ref "C12") (pin "1") (pinfunction "1_1") (pintype "passive"))
      (node (ref "R27") (pin "1") (pinfunction "1_1") (pintype "passive"))
      (node (ref "R28") (pin "2") (pinfunction "2_2") (pintype "passive"))
    )
    (net (code "60") (name "Net-(C14-Pad1)") (class "Default")
      (node (ref "C14") (pin "1") (pinfunction "1_1") (pintype "passive"))
      (node (ref "R31") (pin "1") (pinfunction "1_1") (pintype "passive"))
      (node (ref "R32") (pin "2") (pinfunction "2_2") (pintype "passive"))
    )
    (net (code "61") (name "Net-(C16-Pad1)") (class "Default")
      (node (ref "C16") (pin "1") (pinfunction "1_1") (pintype "passive"))
      (node (ref "R35") (pin "1") (pinfunction "1_1") (pintype "passive"))
      (node (ref "R36") (pin "2") (pinfunction "2_2") (pintype "passive"))
    )
    (net (code "62") (name "Net-(C18-Pad1)") (class "Default")
      (node (ref "C18") (pin "1") (pinfunction "1_1") (pintype "passive"))
      (node (ref "R39") (pin "1") (pinfunction "1_1") (pintype "passive"))
      (node (ref "R40") (pin "2") (pinfunction "2_2") (pintype "passive"))
    )
    (net (code "63") (name "Net-(C22-Pad1)") (class "Default")
      (node (ref "C22") (pin "1") (pinfunction "1_1") (pintype "passive"))
      (node (ref "R58") (pin "2") (pinfunction "2_2") (pintype "passive"))
      (node (ref "R59") (pin "1") (pinfunction "1_1") (pintype "passive"))
    )
    (net (code "64") (name "Net-(C24-Pad1)") (class "Default")
      (node (ref "C24") (pin "1") (pinfunction "1_1") (pintype "passive"))
      (node (ref "R61") (pin "2") (pinfunction "2_2") (pintype "passive"))
      (node (ref "R62") (pin "1") (pinfunction "1_1") (pintype "passive"))
    )
    (net (code "65") (name "Net-(C26-Pad1)") (class "Default")
      (node (ref "C26") (pin "1") (pinfunction "1_1") (pintype "passive"))
      (node (ref "R64") (pin "2") (pinfunction "2_2") (pintype "passive"))
      (node (ref "R65") (pin "1") (pinfunction "1_1") (pintype "passive"))
    )
    (net (code "66") (name "Net-(CON_LC1A-SK-Pad1)") (class "Default")
      (node (ref "CON_LC1") (pin "1") (pinfunction "SK_1") (pintype "passive"))
      (node (ref "CON_LC1") (pin "2") (pinfunction "SK_2") (pintype "passive"))
      (node (ref "FS7") (pin "P$1") (pinfunction "1_P$1") (pintype "passive"))
      (node (ref "FS7") (pin "P$2") (pinfunction "1_P$2") (pintype "passive"))
    )
    (net (code "67") (name "Net-(CON_LC2A-SK-Pad1)") (class "Default")
      (node (ref "CON_LC2") (pin "1") (pinfunction "SK_1") (pintype "passive"))
      (node (ref "CON_LC2") (pin "2") (pinfunction "SK_2") (pintype "passive"))
      (node (ref "FS8") (pin "P$1") (pinfunction "1_P$1") (pintype "passive"))
      (node (ref "FS8") (pin "P$2") (pinfunction "1_P$2") (pintype "passive"))
    )
    (net (code "68") (name "Net-(CON_LC3A-SK-Pad1)") (class "Default")
      (node (ref "CON_LC3") (pin "1") (pinfunction "SK_1") (pintype "passive"))
      (node (ref "CON_LC3") (pin "2") (pinfunction "SK_2") (pintype "passive"))
      (node (ref "FS9") (pin "P$1") (pinfunction "1_P$1") (pintype "passive"))
      (node (ref "FS9") (pin "P$2") (pinfunction "1_P$2") (pintype "passive"))
    )
    (net (code "69") (name "Net-(CON_LC4A-SK-Pad1)") (class "Default")
      (node (ref "CON_LC4") (pin "1") (pinfunction "SK_1") (pintype "passive"))
      (node (ref "CON_LC4") (pin "2") (pinfunction "SK_2") (pintype "passive"))
      (node (ref "FS10") (pin "P$1") (pinfunction "1_P$1") (pintype "passive"))
      (node (ref "FS10") (pin "P$2") (pinfunction "1_P$2") (pintype "passive"))
    )
    (net (code "70") (name "Net-(CON_PT1A-SK-Pad1)") (class "Default")
      (node (ref "CON_PT1") (pin "1") (pinfunction "SK_1") (pintype "passive"))
      (node (ref "CON_PT1") (pin "2") (pinfunction "SK_2") (pintype "passive"))
      (node (ref "FS11") (pin "P$1") (pinfunction "1_P$1") (pintype "passive"))
      (node (ref "FS11") (pin "P$2") (pinfunction "1_P$2") (pintype "passive"))
    )
    (net (code "71") (name "Net-(CON_PT2A-SK-Pad1)") (class "Default")
      (node (ref "CON_PT2") (pin "1") (pinfunction "SK_1") (pintype "passive"))
      (node (ref "CON_PT2") (pin "2") (pinfunction "SK_2") (pintype "passive"))
      (node (ref "FS12") (pin "P$1") (pinfunction "1_P$1") (pintype "passive"))
      (node (ref "FS12") (pin "P$2") (pinfunction "1_P$2") (pintype "passive"))
    )
    (net (code "72") (name "Net-(CON_PT3A-SK-Pad1)") (class "Default")
      (node (ref "CON_PT3") (pin "1") (pinfunction "SK_1") (pintype "passive"))
      (node (ref "CON_PT3") (pin "2") (pinfunction "SK_2") (pintype "passive"))
      (node (ref "FS13") (pin "P$1") (pinfunction "1_P$1") (pintype "passive"))
      (node (ref "FS13") (pin "P$2") (pinfunction "1_P$2") (pintype "passive"))
    )
    (net (code "73") (name "Net-(CON_PT4A-SK-Pad1)") (class "Default")
      (node (ref "CON_PT4") (pin "1") (pinfunction "SK_1") (pintype "passive"))
      (node (ref "CON_PT4") (pin "2") (pinfunction "SK_2") (pintype "passive"))
      (node (ref "FS14") (pin "P$1") (pinfunction "1_P$1") (pintype "passive"))
      (node (ref "FS14") (pin "P$2") (pinfunction "1_P$2") (pintype "passive"))
    )
    (net (code "74") (name "Net-(CON_TC1A-SK-Pad1)") (class "Default")
      (node (ref "CON_TC1") (pin "1") (pinfunction "SK_1") (pintype "passive"))
      (node (ref "CON_TC1") (pin "2") (pinfunction "SK_2") (pintype "passive"))
      (node (ref "FS15") (pin "P$1") (pinfunction "1_P$1") (pintype "passive"))
      (node (ref "FS15") (pin "P$2") (pinfunction "1_P$2") (pintype "passive"))
    )
    (net (code "75") (name "Net-(CON_TC2A-SK-Pad1)") (class "Default")
      (node (ref "CON_TC2") (pin "1") (pinfunction "SK_1") (pintype "passive"))
      (node (ref "CON_TC2") (pin "2") (pinfunction "SK_2") (pintype "passive"))
      (node (ref "FS16") (pin "P$1") (pinfunction "1_P$1") (pintype "passive"))
      (node (ref "FS16") (pin "P$2") (pinfunction "1_P$2") (pintype "passive"))
    )
    (net (code "76") (name "Net-(CON_TC3A-SK-Pad1)") (class "Default")
      (node (ref "CON_TC3") (pin "1") (pinfunction "SK_1") (pintype "passive"))
      (node (ref "CON_TC3") (pin "2") (pinfunction "SK_2") (pintype "passive"))
      (node (ref "FS17") (pin "P$1") (pinfunction "1_P$1") (pintype "passive"))
      (node (ref "FS17") (pin "P$2") (pinfunction "1_P$2") (pintype "passive"))
    )
    (net (code "77") (name "Net-(CON_TC4A-SK-Pad1)") (class "Default")
      (node (ref "CON_TC4") (pin "1") (pinfunction "SK_1") (pintype "passive"))
      (node (ref "CON_TC4") (pin "2") (pinfunction "SK_2") (pintype "passive"))
      (node (ref "FS18") (pin "P$1") (pinfunction "1_P$1") (pintype "passive"))
      (node (ref "FS18") (pin "P$2") (pinfunction "1_P$2") (pintype "passive"))
    )
    (net (code "78") (name "Net-(DRV_STAT_1-PadC)") (class "Default")
      (node (ref "DRV_STAT_1") (pin "C") (pinfunction "C_C") (pintype "passive"))
      (node (ref "R9") (pin "2") (pinfunction "2_2") (pintype "passive"))
    )
    (net (code "79") (name "Net-(DRV_STAT_2-PadC)") (class "Default")
      (node (ref "DRV_STAT_2") (pin "C") (pinfunction "C_C") (pintype "passive"))
      (node (ref "R12") (pin "2") (pinfunction "2_2") (pintype "passive"))
    )
    (net (code "80") (name "Net-(DRV_STAT_3-PadC)") (class "Default")
      (node (ref "DRV_STAT_3") (pin "C") (pinfunction "C_C") (pintype "passive"))
      (node (ref "R15") (pin "2") (pinfunction "2_2") (pintype "passive"))
    )
    (net (code "81") (name "Net-(DRV_STAT_4-PadC)") (class "Default")
      (node (ref "DRV_STAT_4") (pin "C") (pinfunction "C_C") (pintype "passive"))
      (node (ref "R18") (pin "2") (pinfunction "2_2") (pintype "passive"))
    )
    (net (code "82") (name "Net-(DRV_STAT_5-PadC)") (class "Default")
      (node (ref "DRV_STAT_5") (pin "C") (pinfunction "C_C") (pintype "passive"))
      (node (ref "R21") (pin "2") (pinfunction "2_2") (pintype "passive"))
    )
    (net (code "83") (name "Net-(DRV_STAT_6-PadC)") (class "Default")
      (node (ref "DRV_STAT_6") (pin "C") (pinfunction "C_C") (pintype "passive"))
      (node (ref "R24") (pin "2") (pinfunction "2_2") (pintype "passive"))
    )
    (net (code "84") (name "Net-(FS_STAT_1-PadC)") (class "Default")
      (node (ref "FS_STAT_1") (pin "C") (pinfunction "C_C") (pintype "passive"))
      (node (ref "R8") (pin "2") (pinfunction "2_2") (pintype "passive"))
    )
    (net (code "85") (name "Net-(FS_STAT_2-PadC)") (class "Default")
      (node (ref "FS_STAT_2") (pin "C") (pinfunction "C_C") (pintype "passive"))
      (node (ref "R11") (pin "2") (pinfunction "2_2") (pintype "passive"))
    )
    (net (code "86") (name "Net-(FS_STAT_3-PadC)") (class "Default")
      (node (ref "FS_STAT_3") (pin "C") (pinfunction "C_C") (pintype "passive"))
      (node (ref "R14") (pin "2") (pinfunction "2_2") (pintype "passive"))
    )
    (net (code "87") (name "Net-(FS_STAT_4-PadC)") (class "Default")
      (node (ref "FS_STAT_4") (pin "C") (pinfunction "C_C") (pintype "passive"))
      (node (ref "R17") (pin "2") (pinfunction "2_2") (pintype "passive"))
    )
    (net (code "88") (name "Net-(FS_STAT_5-PadC)") (class "Default")
      (node (ref "FS_STAT_5") (pin "C") (pinfunction "C_C") (pintype "passive"))
      (node (ref "R20") (pin "2") (pinfunction "2_2") (pintype "passive"))
    )
    (net (code "89") (name "Net-(FS_STAT_6-PadC)") (class "Default")
      (node (ref "FS_STAT_6") (pin "C") (pinfunction "C_C") (pintype "passive"))
      (node (ref "R23") (pin "2") (pinfunction "2_2") (pintype "passive"))
    )
    (net (code "90") (name "Net-(HBT-PadC)") (class "Default")
      (node (ref "HBT") (pin "C") (pinfunction "C_C") (pintype "passive"))
      (node (ref "R77") (pin "2") (pinfunction "2_2") (pintype "passive"))
    )
    (net (code "91") (name "Net-(IC1-FG)") (class "Default")
      (node (ref "IC1") (pin "1") (pinfunction "FG_1") (pintype "input"))
      (node (ref "RF1") (pin "2") (pinfunction "2_2") (pintype "passive"))
    )
    (net (code "92") (name "Net-(IC1-REF)") (class "Default")
      (node (ref "IC1") (pin "5") (pinfunction "REF_5") (pintype "input"))
      (node (ref "R78") (pin "S") (pinfunction "S_S") (pintype "passive"))
      (node (ref "RG1") (pin "1") (pinfunction "1_1") (pintype "passive"))
    )
    (net (code "93") (name "Net-(IC2-FG)") (class "Default")
      (node (ref "IC2") (pin "1") (pinfunction "FG_1") (pintype "input"))
      (node (ref "RF2") (pin "2") (pinfunction "2_2") (pintype "passive"))
    )
    (net (code "94") (name "Net-(IC2-REF)") (class "Default")
      (node (ref "IC2") (pin "5") (pinfunction "REF_5") (pintype "input"))
      (node (ref "R48") (pin "S") (pinfunction "S_S") (pintype "passive"))
      (node (ref "RG2") (pin "1") (pinfunction "1_1") (pintype "passive"))
    )
    (net (code "95") (name "Net-(IC3-FG)") (class "Default")
      (node (ref "IC3") (pin "1") (pinfunction "FG_1") (pintype "input"))
      (node (ref "RF3") (pin "2") (pinfunction "2_2") (pintype "passive"))
    )
    (net (code "96") (name "Net-(IC3-REF)") (class "Default")
      (node (ref "IC3") (pin "5") (pinfunction "REF_5") (pintype "input"))
      (node (ref "R46") (pin "S") (pinfunction "S_S") (pintype "passive"))
      (node (ref "RG3") (pin "1") (pinfunction "1_1") (pintype "passive"))
    )
    (net (code "97") (name "Net-(IC4-FG)") (class "Default")
      (node (ref "IC4") (pin "1") (pinfunction "FG_1") (pintype "input"))
      (node (ref "RF4") (pin "2") (pinfunction "2_2") (pintype "passive"))
    )
    (net (code "98") (name "Net-(IC4-REF)") (class "Default")
      (node (ref "IC4") (pin "5") (pinfunction "REF_5") (pintype "input"))
      (node (ref "R47") (pin "S") (pinfunction "S_S") (pintype "passive"))
      (node (ref "RG4") (pin "1") (pinfunction "1_1") (pintype "passive"))
    )
    (net (code "99") (name "Net-(IC5A-+IN)") (class "Default")
      (node (ref "C13") (pin "1") (pinfunction "1_1") (pintype "passive"))
      (node (ref "IC5") (pin "3") (pinfunction "+IN_3") (pintype "input"))
      (node (ref "R27") (pin "2") (pinfunction "2_2") (pintype "passive"))
    )
    (net (code "100") (name "Net-(IC5A--IN)") (class "Default")
      (node (ref "IC5") (pin "2") (pinfunction "-IN_2") (pintype "input"))
      (node (ref "R25") (pin "1") (pinfunction "1_1") (pintype "passive"))
      (node (ref "R26") (pin "2") (pinfunction "2_2") (pintype "passive"))
    )
    (net (code "101") (name "Net-(IC5B-+IN)") (class "Default")
      (node (ref "C15") (pin "1") (pinfunction "1_1") (pintype "passive"))
      (node (ref "IC5") (pin "5") (pinfunction "+IN_5") (pintype "input"))
      (node (ref "R31") (pin "2") (pinfunction "2_2") (pintype "passive"))
    )
    (net (code "102") (name "Net-(IC5B--IN)") (class "Default")
      (node (ref "IC5") (pin "6") (pinfunction "-IN_6") (pintype "input"))
      (node (ref "R29") (pin "1") (pinfunction "1_1") (pintype "passive"))
      (node (ref "R30") (pin "2") (pinfunction "2_2") (pintype "passive"))
    )
    (net (code "103") (name "Net-(IC5C-+IN)") (class "Default")
      (node (ref "C17") (pin "1") (pinfunction "1_1") (pintype "passive"))
      (node (ref "IC5") (pin "10") (pinfunction "+IN_10") (pintype "input"))
      (node (ref "R35") (pin "2") (pinfunction "2_2") (pintype "passive"))
    )
    (net (code "104") (name "Net-(IC5C--IN)") (class "Default")
      (node (ref "IC5") (pin "9") (pinfunction "-IN_9") (pintype "input"))
      (node (ref "R33") (pin "1") (pinfunction "1_1") (pintype "passive"))
      (node (ref "R34") (pin "2") (pinfunction "2_2") (pintype "passive"))
    )
    (net (code "105") (name "Net-(IC5D-+IN)") (class "Default")
      (node (ref "C19") (pin "1") (pinfunction "1_1") (pintype "passive"))
      (node (ref "IC5") (pin "12") (pinfunction "+IN_12") (pintype "input"))
      (node (ref "R39") (pin "2") (pinfunction "2_2") (pintype "passive"))
    )
    (net (code "106") (name "Net-(IC5D--IN)") (class "Default")
      (node (ref "IC5") (pin "13") (pinfunction "-IN_13") (pintype "input"))
      (node (ref "R37") (pin "1") (pinfunction "1_1") (pintype "passive"))
      (node (ref "R38") (pin "2") (pinfunction "2_2") (pintype "passive"))
    )
    (net (code "107") (name "Net-(IC6A-+IN)") (class "Default")
      (node (ref "C1") (pin "1") (pinfunction "1_1") (pintype "passive"))
      (node (ref "IC6") (pin "3") (pinfunction "+IN_3") (pintype "input"))
      (node (ref "R56") (pin "2") (pinfunction "2_2") (pintype "passive"))
    )
    (net (code "108") (name "Net-(IC6A--IN)") (class "Default")
      (node (ref "IC6") (pin "2") (pinfunction "-IN_2") (pintype "input"))
      (node (ref "R66") (pin "1") (pinfunction "1_1") (pintype "passive"))
      (node (ref "R67") (pin "2") (pinfunction "2_2") (pintype "passive"))
    )
    (net (code "109") (name "Net-(IC6B-+IN)") (class "Default")
      (node (ref "C21") (pin "1") (pinfunction "1_1") (pintype "passive"))
      (node (ref "IC6") (pin "5") (pinfunction "+IN_5") (pintype "input"))
      (node (ref "R59") (pin "2") (pinfunction "2_2") (pintype "passive"))
    )
    (net (code "110") (name "Net-(IC6B--IN)") (class "Default")
      (node (ref "IC6") (pin "6") (pinfunction "-IN_6") (pintype "input"))
      (node (ref "R68") (pin "1") (pinfunction "1_1") (pintype "passive"))
      (node (ref "R69") (pin "2") (pinfunction "2_2") (pintype "passive"))
    )
    (net (code "111") (name "Net-(IC6C-+IN)") (class "Default")
      (node (ref "C23") (pin "1") (pinfunction "1_1") (pintype "passive"))
      (node (ref "IC6") (pin "10") (pinfunction "+IN_10") (pintype "input"))
      (node (ref "R62") (pin "2") (pinfunction "2_2") (pintype "passive"))
    )
    (net (code "112") (name "Net-(IC6C--IN)") (class "Default")
      (node (ref "IC6") (pin "9") (pinfunction "-IN_9") (pintype "input"))
      (node (ref "R70") (pin "1") (pinfunction "1_1") (pintype "passive"))
      (node (ref "R71") (pin "2") (pinfunction "2_2") (pintype "passive"))
    )
    (net (code "113") (name "Net-(IC6D-+IN)") (class "Default")
      (node (ref "C25") (pin "1") (pinfunction "1_1") (pintype "passive"))
      (node (ref "IC6") (pin "12") (pinfunction "+IN_12") (pintype "input"))
      (node (ref "R65") (pin "2") (pinfunction "2_2") (pintype "passive"))
    )
    (net (code "114") (name "Net-(IC6D--IN)") (class "Default")
      (node (ref "IC6") (pin "13") (pinfunction "-IN_13") (pintype "input"))
      (node (ref "R72") (pin "1") (pinfunction "1_1") (pintype "passive"))
      (node (ref "R73") (pin "2") (pinfunction "2_2") (pintype "passive"))
    )
    (net (code "115") (name "Net-(PWR_5V-PadC)") (class "Default")
      (node (ref "PWR_5V") (pin "C") (pinfunction "C_C") (pintype "passive"))
      (node (ref "R4") (pin "2") (pinfunction "2_2") (pintype "passive"))
    )
    (net (code "116") (name "Net-(PWR_10V-PadC)") (class "Default")
      (node (ref "PWR_10V") (pin "C") (pinfunction "C_C") (pintype "passive"))
      (node (ref "R5") (pin "2") (pinfunction "2_2") (pintype "passive"))
    )
    (net (code "117") (name "Net-(PWR_12V-PadC)") (class "Default")
      (node (ref "PWR_12V") (pin "C") (pinfunction "C_C") (pintype "passive"))
      (node (ref "R6") (pin "2") (pinfunction "2_2") (pintype "passive"))
    )
    (net (code "118") (name "Net-(SW2-O)") (class "Default")
      (node (ref "CON_FAN") (pin "1") (pinfunction "SK_1") (pintype "passive"))
      (node (ref "CON_FAN") (pin "2") (pinfunction "SK_2") (pintype "passive"))
      (node (ref "SW2") (pin "1") (pinfunction "O_1") (pintype "passive"))
    )
    (net (code "119") (name "PT1-") (class "Default")
      (node (ref "CON_PT1") (pin "3") (pinfunction "SK_3") (pintype "passive"))
      (node (ref "CON_PT1") (pin "4") (pinfunction "SK_4") (pintype "passive"))
      (node (ref "JP4") (pin "1") (pinfunction "1_1") (pintype "passive"))
      (node (ref "R54") (pin "2") (pinfunction "2_2") (pintype "passive"))
      (node (ref "R55") (pin "1") (pinfunction "1_1") (pintype "passive"))
    )
    (net (code "120") (name "PT1_CAL") (class "Default")
      (node (ref "ADC2") (pin "1") (pinfunction "CH0_1") (pintype "bidirectional"))
      (node (ref "C2") (pin "2") (pinfunction "2_2") (pintype "passive"))
      (node (ref "IC6") (pin "1") (pinfunction "OUT_1") (pintype "output"))
      (node (ref "JP3") (pin "1") (pinfunction "1_1") (pintype "passive"))
      (node (ref "R66") (pin "2") (pinfunction "2_2") (pintype "passive"))
    )
    (net (code "121") (name "PT2-") (class "Default")
      (node (ref "CON_PT2") (pin "3") (pinfunction "SK_3") (pintype "passive"))
      (node (ref "CON_PT2") (pin "4") (pinfunction "SK_4") (pintype "passive"))
      (node (ref "JP4") (pin "2") (pinfunction "2_2") (pintype "passive"))
      (node (ref "R57") (pin "2") (pinfunction "2_2") (pintype "passive"))
      (node (ref "R58") (pin "1") (pinfunction "1_1") (pintype "passive"))
    )
    (net (code "122") (name "PT2_CAL") (class "Default")
      (node (ref "ADC2") (pin "2") (pinfunction "CH1_2") (pintype "bidirectional"))
      (node (ref "C22") (pin "2") (pinfunction "2_2") (pintype "passive"))
      (node (ref "IC6") (pin "7") (pinfunction "OUT_7") (pintype "output"))
      (node (ref "JP3") (pin "2") (pinfunction "2_2") (pintype "passive"))
      (node (ref "R68") (pin "2") (pinfunction "2_2") (pintype "passive"))
    )
    (net (code "123") (name "PT3-") (class "Default")
      (node (ref "CON_PT3") (pin "3") (pinfunction "SK_3") (pintype "passive"))
      (node (ref "CON_PT3") (pin "4") (pinfunction "SK_4") (pintype "passive"))
      (node (ref "JP4") (pin "3") (pinfunction "3_3") (pintype "passive"))
      (node (ref "R60") (pin "2") (pinfunction "2_2") (pintype "passive"))
      (node (ref "R61") (pin "1") (pinfunction "1_1") (pintype "passive"))
    )
    (net (code "124") (name "PT3_CAL") (class "Default")
      (node (ref "ADC2") (pin "3") (pinfunction "CH2_3") (pintype "bidirectional"))
      (node (ref "C24") (pin "2") (pinfunction "2_2") (pintype "passive"))
      (node (ref "IC6") (pin "8") (pinfunction "OUT_8") (pintype "output"))
      (node (ref "JP3") (pin "3") (pinfunction "3_3") (pintype "passive"))
      (node (ref "R70") (pin "2") (pinfunction "2_2") (pintype "passive"))
    )
    (net (code "125") (name "PT4-") (class "Default")
      (node (ref "CON_PT4") (pin "3") (pinfunction "SK_3") (pintype "passive"))
      (node (ref "CON_PT4") (pin "4") (pinfunction "SK_4") (pintype "passive"))
      (node (ref "JP4") (pin "4") (pinfunction "4_4") (pintype "passive"))
      (node (ref "R63") (pin "2") (pinfunction "2_2") (pintype "passive"))
      (node (ref "R64") (pin "1") (pinfunction "1_1") (pintype "passive"))
    )
    (net (code "126") (name "PT4_CAL") (class "Default")
      (node (ref "ADC2") (pin "4") (pinfunction "CH3_4") (pintype "bidirectional"))
      (node (ref "C26") (pin "2") (pinfunction "2_2") (pintype "passive"))
      (node (ref "IC6") (pin "14") (pinfunction "OUT_14") (pintype "output"))
      (node (ref "JP3") (pin "4") (pinfunction "4_4") (pintype "passive"))
      (node (ref "R72") (pin "2") (pinfunction "2_2") (pintype "passive"))
    )
    (net (code "127") (name "SPI_CLK") (class "Default")
      (node (ref "ADC1") (pin "13") (pinfunction "CLK_13") (pintype "bidirectional"))
      (node (ref "ADC2") (pin "13") (pinfunction "CLK_13") (pintype "bidirectional"))
      (node (ref "ADC3") (pin "13") (pinfunction "CLK_13") (pintype "bidirectional"))
      (node (ref "X1") (pin "23") (pinfunction "KL_23") (pintype "passive"))
    )
    (net (code "128") (name "SPI_MISO") (class "Default")
      (node (ref "ADC1") (pin "12") (pinfunction "DOUT_12") (pintype "bidirectional"))
      (node (ref "ADC2") (pin "12") (pinfunction "DOUT_12") (pintype "bidirectional"))
      (node (ref "ADC3") (pin "12") (pinfunction "DOUT_12") (pintype "bidirectional"))
      (node (ref "X1") (pin "21") (pinfunction "KL_21") (pintype "passive"))
    )
    (net (code "129") (name "SPI_MOSI") (class "Default")
      (node (ref "ADC1") (pin "11") (pinfunction "DIN_11") (pintype "bidirectional"))
      (node (ref "ADC2") (pin "11") (pinfunction "DIN_11") (pintype "bidirectional"))
      (node (ref "ADC3") (pin "11") (pinfunction "DIN_11") (pintype "bidirectional"))
      (node (ref "X1") (pin "19") (pinfunction "KL_19") (pintype "passive"))
    )
    (net (code "130") (name "TC1") (class "Default")
      (node (ref "ADC3") (pin "1") (pinfunction "CH0_1") (pintype "bidirectional"))
      (node (ref "CON_TC1") (pin "3") (pinfunction "SK_3") (pintype "passive"))
      (node (ref "CON_TC1") (pin "4") (pinfunction "SK_4") (pintype "passive"))
      (node (ref "JP1") (pin "1") (pinfunction "1_1") (pintype "passive"))
    )
    (net (code "131") (name "TC2") (class "Default")
      (node (ref "ADC3") (pin "2") (pinfunction "CH1_2") (pintype "bidirectional"))
      (node (ref "CON_TC2") (pin "3") (pinfunction "SK_3") (pintype "passive"))
      (node (ref "CON_TC2") (pin "4") (pinfunction "SK_4") (pintype "passive"))
      (node (ref "JP1") (pin "2") (pinfunction "2_2") (pintype "passive"))
    )
    (net (code "132") (name "TC3") (class "Default")
      (node (ref "ADC3") (pin "3") (pinfunction "CH2_3") (pintype "bidirectional"))
      (node (ref "CON_TC3") (pin "3") (pinfunction "SK_3") (pintype "passive"))
      (node (ref "CON_TC3") (pin "4") (pinfunction "SK_4") (pintype "passive"))
      (node (ref "JP1") (pin "3") (pinfunction "3_3") (pintype "passive"))
    )
    (net (code "133") (name "TC4") (class "Default")
      (node (ref "ADC3") (pin "4") (pinfunction "CH3_4") (pintype "bidirectional"))
      (node (ref "CON_TC4") (pin "3") (pinfunction "SK_3") (pintype "passive"))
      (node (ref "CON_TC4") (pin "4") (pinfunction "SK_4") (pintype "passive"))
      (node (ref "JP1") (pin "4") (pinfunction "4_4") (pintype "passive"))
    )
    (net (code "134") (name "unconnected-(JP7-Pad7)") (class "Default")
      (node (ref "JP7") (pin "7") (pinfunction "7_7") (pintype "passive"))
    )
    (net (code "135") (name "unconnected-(JP7-Pad8)") (class "Default")
      (node (ref "JP7") (pin "8") (pinfunction "8_8") (pintype "passive"))
    )
    (net (code "136") (name "unconnected-(JP8-Pad1)") (class "Default")
      (node (ref "JP8") (pin "1") (pinfunction "1_1") (pintype "passive"))
    )
    (net (code "137") (name "unconnected-(SW1-S-Pad3)") (class "Default")
      (node (ref "SW1") (pin "3") (pinfunction "S_3") (pintype "passive"))
    )
    (net (code "138") (name "unconnected-(SW2-S-Pad3)") (class "Default")
      (node (ref "SW2") (pin "3") (pinfunction "S_3") (pintype "passive"))
    )
    (net (code "139") (name "unconnected-(X1A-KL-Pad1)") (class "Default")
      (node (ref "X1") (pin "1") (pinfunction "KL_1") (pintype "passive"))
    )
    (net (code "140") (name "unconnected-(X1AC-KL-Pad35)") (class "Default")
      (node (ref "X1") (pin "35") (pinfunction "KL_35") (pintype "passive"))
    )
    (net (code "141") (name "unconnected-(X1AD-KL-Pad36)") (class "Default")
      (node (ref "X1") (pin "36") (pinfunction "KL_36") (pintype "passive"))
    )
    (net (code "142") (name "unconnected-(X1AE-KL-Pad37)") (class "Default")
      (node (ref "X1") (pin "37") (pinfunction "KL_37") (pintype "passive"))
    )
    (net (code "143") (name "unconnected-(X1AF-KL-Pad38)") (class "Default")
      (node (ref "X1") (pin "38") (pinfunction "KL_38") (pintype "passive"))
    )
    (net (code "144") (name "unconnected-(X1AI-KL-Pad40)") (class "Default")
      (node (ref "X1") (pin "40") (pinfunction "KL_40") (pintype "passive"))
    )
    (net (code "145") (name "unconnected-(X1AJ-KL-Pad5)") (class "Default")
      (node (ref "X1") (pin "5") (pinfunction "KL_5") (pintype "passive"))
    )
    (net (code "146") (name "unconnected-(X1AL-KL-Pad7)") (class "Default")
      (node (ref "X1") (pin "7") (pinfunction "KL_7") (pintype "passive"))
    )
    (net (code "147") (name "unconnected-(X1AM-KL-Pad8)") (class "Default")
      (node (ref "X1") (pin "8") (pinfunction "KL_8") (pintype "passive"))
    )
    (net (code "148") (name "unconnected-(X1B-KL-Pad10)") (class "Default")
      (node (ref "X1") (pin "10") (pinfunction "KL_10") (pintype "passive"))
    )
    (net (code "149") (name "unconnected-(X1D-KL-Pad12)") (class "Default")
      (node (ref "X1") (pin "12") (pinfunction "KL_12") (pintype "passive"))
    )
    (net (code "150") (name "unconnected-(X1H-KL-Pad16)") (class "Default")
      (node (ref "X1") (pin "16") (pinfunction "KL_16") (pintype "passive"))
    )
    (net (code "151") (name "unconnected-(X1I-KL-Pad17)") (class "Default")
      (node (ref "X1") (pin "17") (pinfunction "KL_17") (pintype "passive"))
    )
    (net (code "152") (name "unconnected-(X1T-KL-Pad27)") (class "Default")
      (node (ref "X1") (pin "27") (pinfunction "KL_27") (pintype "passive"))
    )
    (net (code "153") (name "unconnected-(X1U-KL-Pad28)") (class "Default")
      (node (ref "X1") (pin "28") (pinfunction "KL_28") (pintype "passive"))
    )
    (net (code "154") (name "unconnected-(X1W-KL-Pad3)") (class "Default")
      (node (ref "X1") (pin "3") (pinfunction "KL_3") (pintype "passive"))
    )
    (net (code "155") (name "unconnected-(X1Y-KL-Pad31)") (class "Default")
      (node (ref "X1") (pin "31") (pinfunction "KL_31") (pintype "passive"))
    )
  )
)
